# Sheet1.net
KiCad netlist of a schematic drawn in Altium Designer
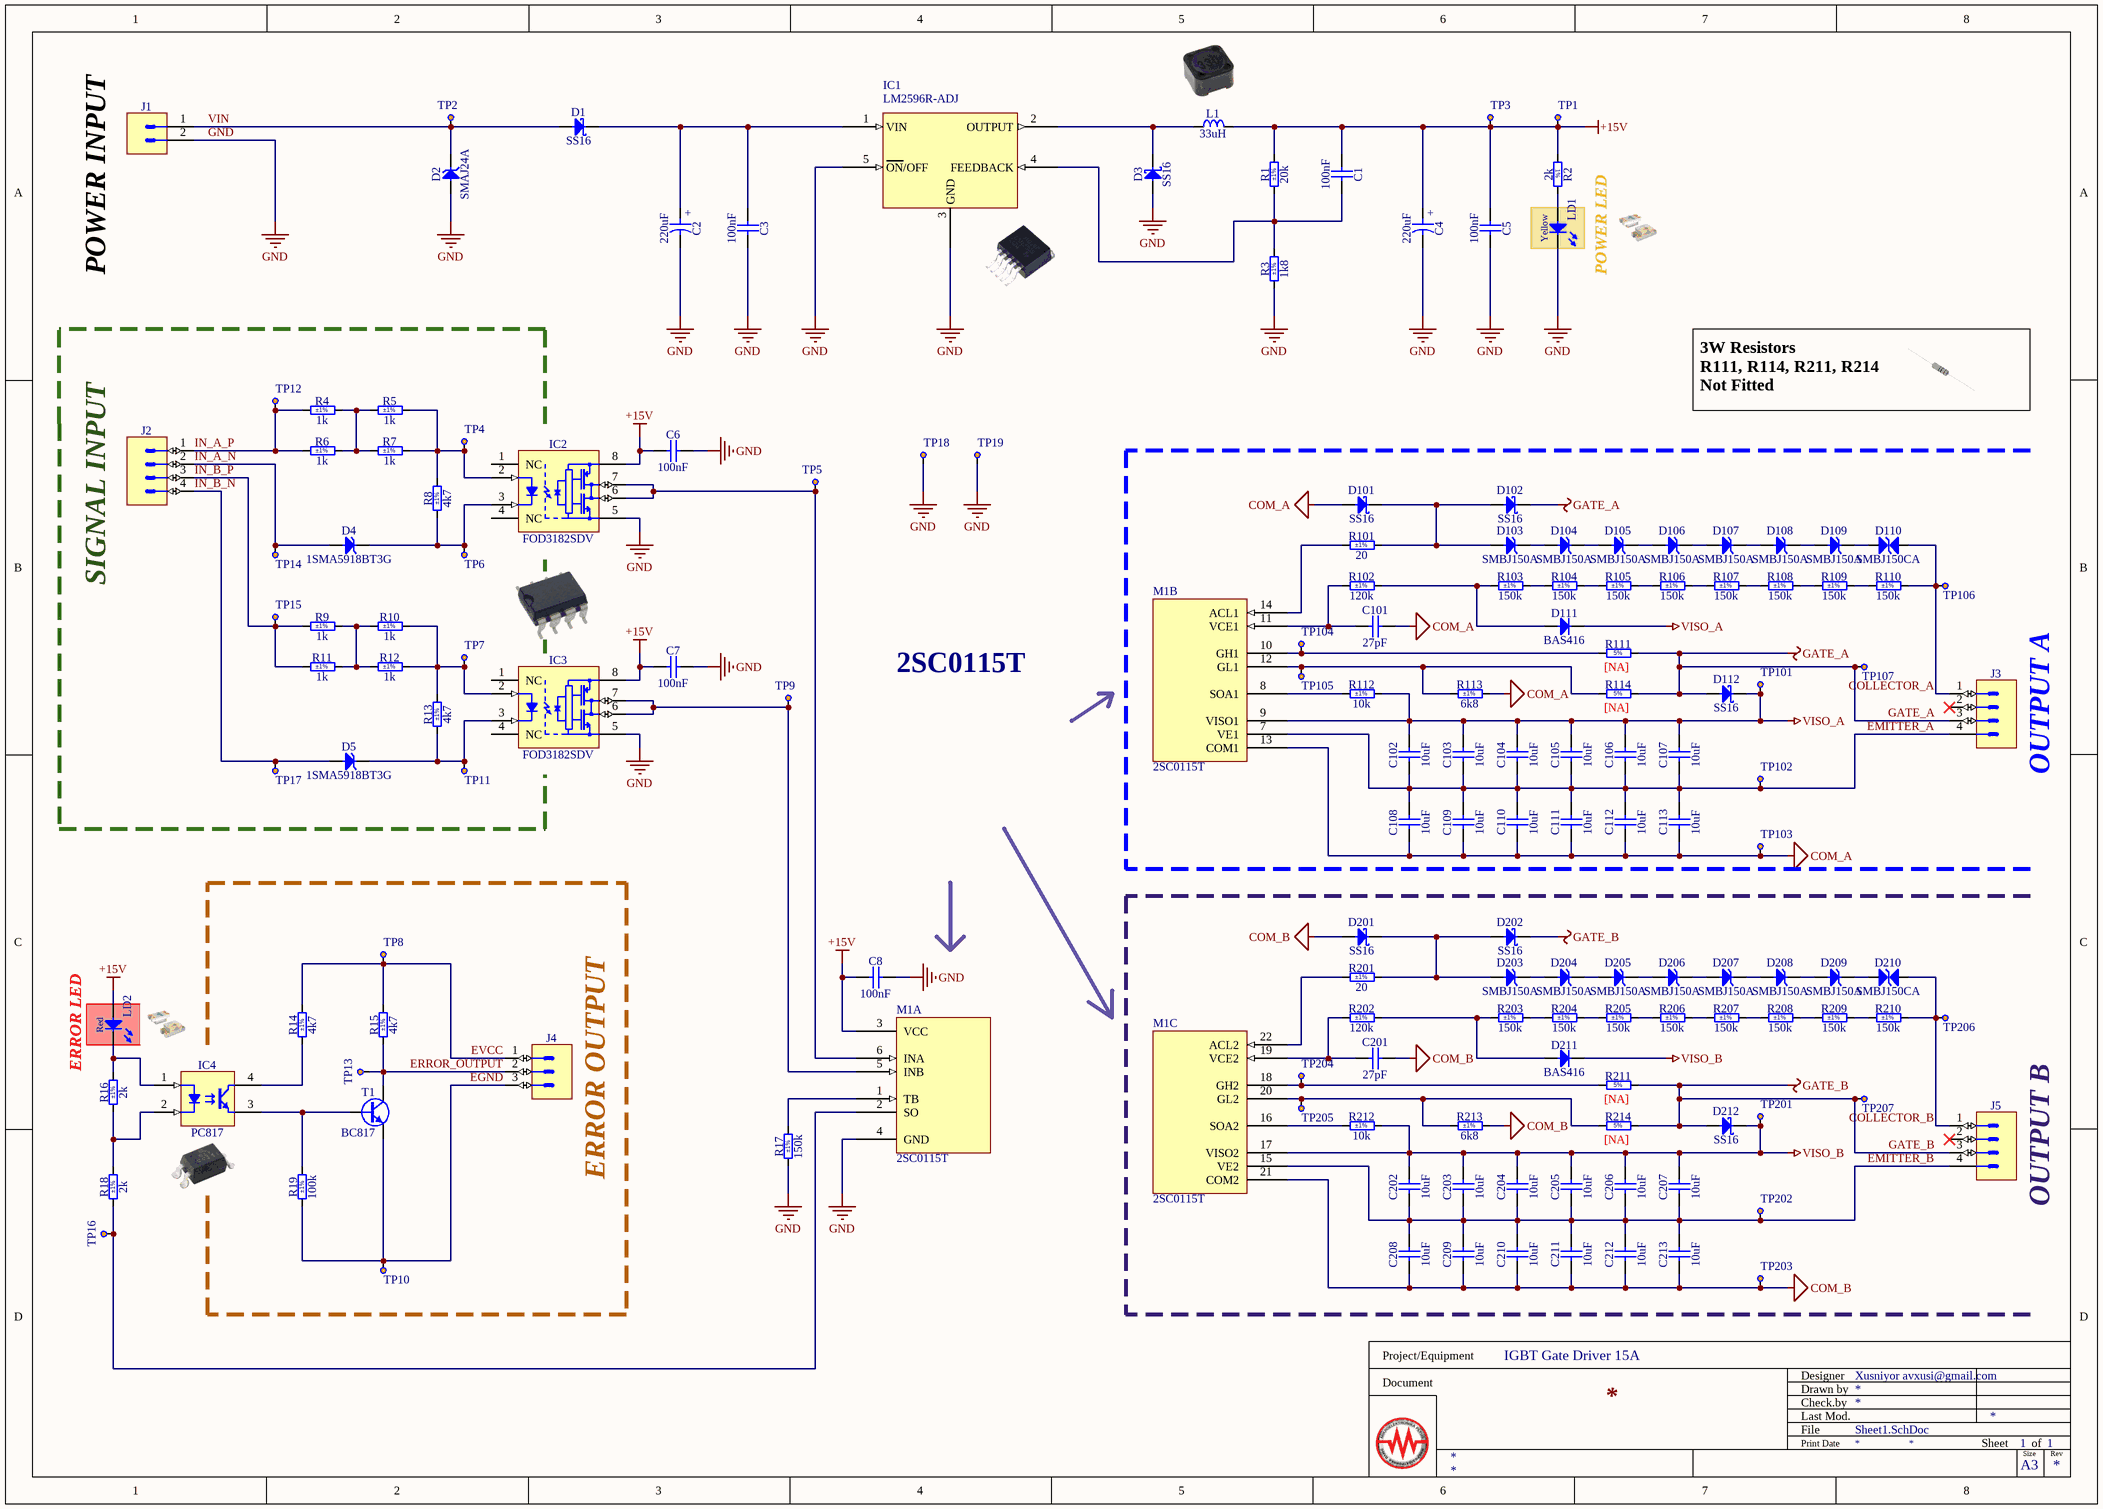
[diagram p0: Sheet1.SchDoc]

(export (version "E")
  (design (tool "Eeschema 10.0.6"))
  (components
    (comp (ref "C1")
      (value "100nF")
      (footprint "CAPC3216X140N")
      (description "Non-polarised capacitor")
      (fields
        (field (name "PART NUMBER") "CC1206_100NF_50V_10%_X7R")
        (field (name "VOLTAGE") "50V")
        (field (name "AUTHOR") "CERN DEM JLC")
      )
      (libsource (lib "Capacitors") (part "Capacitor - non polarized"))
    )
    (comp (ref "C2")
      (value "220uF")
      (footprint "CAPPR500-1050X1750")
      (description "Polarised capacitor")
      (fields
        (field (name "PART NUMBER") "CAER_220UF_35V_20%_500-1050X1750_LESR0R084")
        (field (name "VOLTAGE") "35V")
        (field (name "AUTHOR") "CERN DEM JLC")
      )
      (libsource (lib "Capacitors") (part "Capacitor - polarized"))
    )
    (comp (ref "C3")
      (value "100nF")
      (footprint "CAPC3216X140N")
      (description "Non-polarised capacitor")
      (fields
        (field (name "PART NUMBER") "CC1206_100NF_50V_10%_X7R")
        (field (name "VOLTAGE") "50V")
        (field (name "AUTHOR") "CERN DEM JLC")
      )
      (libsource (lib "Capacitors") (part "Capacitor - non polarized"))
    )
    (comp (ref "C4")
      (value "220uF")
      (footprint "CAPPR500-1050X1750")
      (description "Polarised capacitor")
      (fields
        (field (name "PART NUMBER") "CAER_220UF_35V_20%_500-1050X1750_LESR0R084")
        (field (name "VOLTAGE") "35V")
        (field (name "AUTHOR") "CERN DEM JLC")
      )
      (libsource (lib "Capacitors") (part "Capacitor - polarized"))
    )
    (comp (ref "C5")
      (value "100nF")
      (footprint "CAPC3216X140N")
      (description "Non-polarised capacitor")
      (fields
        (field (name "PART NUMBER") "CC1206_100NF_50V_10%_X7R")
        (field (name "VOLTAGE") "50V")
        (field (name "AUTHOR") "CERN DEM JLC")
      )
      (libsource (lib "Capacitors") (part "Capacitor - non polarized"))
    )
    (comp (ref "C6")
      (value "100nF")
      (footprint "CAPC3216X140N")
      (description "Non-polarised capacitor")
      (fields
        (field (name "PART NUMBER") "CC1206_100NF_50V_10%_X7R")
        (field (name "VOLTAGE") "50V")
        (field (name "AUTHOR") "CERN DEM JLC")
      )
      (libsource (lib "Capacitors") (part "Capacitor - non polarized"))
    )
    (comp (ref "C7")
      (value "100nF")
      (footprint "CAPC3216X140N")
      (description "Non-polarised capacitor")
      (fields
        (field (name "PART NUMBER") "CC1206_100NF_50V_10%_X7R")
        (field (name "VOLTAGE") "50V")
        (field (name "AUTHOR") "CERN DEM JLC")
      )
      (libsource (lib "Capacitors") (part "Capacitor - non polarized"))
    )
    (comp (ref "C8")
      (value "100nF")
      (footprint "CAPC3216X140N")
      (description "Non-polarised capacitor")
      (fields
        (field (name "PART NUMBER") "CC1206_100NF_50V_10%_X7R")
        (field (name "VOLTAGE") "50V")
        (field (name "AUTHOR") "CERN DEM JLC")
      )
      (libsource (lib "Capacitors") (part "Capacitor - non polarized"))
    )
    (comp (ref "C101")
      (value "27pF")
      (footprint "CAPC3216X140N")
      (description "Non-polarised capacitor")
      (fields
        (field (name "PART NUMBER") "CC1206_27PF_50V_5%_NP0")
        (field (name "VOLTAGE") "50V")
        (field (name "AUTHOR") "CERN DEM JLC")
      )
      (libsource (lib "Capacitors") (part "Capacitor - non polarized"))
    )
    (comp (ref "C102")
      (value "10uF")
      (footprint "CAPC3216X180N")
      (description "Non-polarised capacitor")
      (fields
        (field (name "PART NUMBER") "CC1206_10UF_25V_10%_X7R")
        (field (name "VOLTAGE") "25V")
        (field (name "AUTHOR") "CERN DEM JLC")
      )
      (libsource (lib "Capacitors") (part "Capacitor - non polarized"))
    )
    (comp (ref "C103")
      (value "10uF")
      (footprint "CAPC3216X180N")
      (description "Non-polarised capacitor")
      (fields
        (field (name "PART NUMBER") "CC1206_10UF_25V_10%_X7R")
        (field (name "VOLTAGE") "25V")
        (field (name "AUTHOR") "CERN DEM JLC")
      )
      (libsource (lib "Capacitors") (part "Capacitor - non polarized"))
    )
    (comp (ref "C104")
      (value "10uF")
      (footprint "CAPC3216X180N")
      (description "Non-polarised capacitor")
      (fields
        (field (name "PART NUMBER") "CC1206_10UF_25V_10%_X7R")
        (field (name "VOLTAGE") "25V")
        (field (name "AUTHOR") "CERN DEM JLC")
      )
      (libsource (lib "Capacitors") (part "Capacitor - non polarized"))
    )
    (comp (ref "C105")
      (value "10uF")
      (footprint "CAPC3216X180N")
      (description "Non-polarised capacitor")
      (fields
        (field (name "PART NUMBER") "CC1206_10UF_25V_10%_X7R")
        (field (name "VOLTAGE") "25V")
        (field (name "AUTHOR") "CERN DEM JLC")
      )
      (libsource (lib "Capacitors") (part "Capacitor - non polarized"))
    )
    (comp (ref "C106")
      (value "10uF")
      (footprint "CAPC3216X180N")
      (description "Non-polarised capacitor")
      (fields
        (field (name "PART NUMBER") "CC1206_10UF_25V_10%_X7R")
        (field (name "VOLTAGE") "25V")
        (field (name "AUTHOR") "CERN DEM JLC")
      )
      (libsource (lib "Capacitors") (part "Capacitor - non polarized"))
    )
    (comp (ref "C107")
      (value "10uF")
      (footprint "CAPC3216X180N")
      (description "Non-polarised capacitor")
      (fields
        (field (name "PART NUMBER") "CC1206_10UF_25V_10%_X7R")
        (field (name "VOLTAGE") "25V")
        (field (name "AUTHOR") "CERN DEM JLC")
      )
      (libsource (lib "Capacitors") (part "Capacitor - non polarized"))
    )
    (comp (ref "C108")
      (value "10uF")
      (footprint "CAPC3216X180N")
      (description "Non-polarised capacitor")
      (fields
        (field (name "PART NUMBER") "CC1206_10UF_25V_10%_X7R")
        (field (name "VOLTAGE") "25V")
        (field (name "AUTHOR") "CERN DEM JLC")
      )
      (libsource (lib "Capacitors") (part "Capacitor - non polarized"))
    )
    (comp (ref "C109")
      (value "10uF")
      (footprint "CAPC3216X180N")
      (description "Non-polarised capacitor")
      (fields
        (field (name "PART NUMBER") "CC1206_10UF_25V_10%_X7R")
        (field (name "VOLTAGE") "25V")
        (field (name "AUTHOR") "CERN DEM JLC")
      )
      (libsource (lib "Capacitors") (part "Capacitor - non polarized"))
    )
    (comp (ref "C110")
      (value "10uF")
      (footprint "CAPC3216X180N")
      (description "Non-polarised capacitor")
      (fields
        (field (name "PART NUMBER") "CC1206_10UF_25V_10%_X7R")
        (field (name "VOLTAGE") "25V")
        (field (name "AUTHOR") "CERN DEM JLC")
      )
      (libsource (lib "Capacitors") (part "Capacitor - non polarized"))
    )
    (comp (ref "C111")
      (value "10uF")
      (footprint "CAPC3216X180N")
      (description "Non-polarised capacitor")
      (fields
        (field (name "PART NUMBER") "CC1206_10UF_25V_10%_X7R")
        (field (name "VOLTAGE") "25V")
        (field (name "AUTHOR") "CERN DEM JLC")
      )
      (libsource (lib "Capacitors") (part "Capacitor - non polarized"))
    )
    (comp (ref "C112")
      (value "10uF")
      (footprint "CAPC3216X180N")
      (description "Non-polarised capacitor")
      (fields
        (field (name "PART NUMBER") "CC1206_10UF_25V_10%_X7R")
        (field (name "VOLTAGE") "25V")
        (field (name "AUTHOR") "CERN DEM JLC")
      )
      (libsource (lib "Capacitors") (part "Capacitor - non polarized"))
    )
    (comp (ref "C113")
      (value "10uF")
      (footprint "CAPC3216X180N")
      (description "Non-polarised capacitor")
      (fields
        (field (name "PART NUMBER") "CC1206_10UF_25V_10%_X7R")
        (field (name "VOLTAGE") "25V")
        (field (name "AUTHOR") "CERN DEM JLC")
      )
      (libsource (lib "Capacitors") (part "Capacitor - non polarized"))
    )
    (comp (ref "C201")
      (value "27pF")
      (footprint "CAPC3216X140N")
      (description "Non-polarised capacitor")
      (fields
        (field (name "PART NUMBER") "CC1206_27PF_50V_5%_NP0")
        (field (name "VOLTAGE") "50V")
        (field (name "AUTHOR") "CERN DEM JLC")
      )
      (libsource (lib "Capacitors") (part "Capacitor - non polarized"))
    )
    (comp (ref "C202")
      (value "10uF")
      (footprint "CAPC3216X180N")
      (description "Non-polarised capacitor")
      (fields
        (field (name "PART NUMBER") "CC1206_10UF_25V_10%_X7R")
        (field (name "VOLTAGE") "25V")
        (field (name "AUTHOR") "CERN DEM JLC")
      )
      (libsource (lib "Capacitors") (part "Capacitor - non polarized"))
    )
    (comp (ref "C203")
      (value "10uF")
      (footprint "CAPC3216X180N")
      (description "Non-polarised capacitor")
      (fields
        (field (name "PART NUMBER") "CC1206_10UF_25V_10%_X7R")
        (field (name "VOLTAGE") "25V")
        (field (name "AUTHOR") "CERN DEM JLC")
      )
      (libsource (lib "Capacitors") (part "Capacitor - non polarized"))
    )
    (comp (ref "C204")
      (value "10uF")
      (footprint "CAPC3216X180N")
      (description "Non-polarised capacitor")
      (fields
        (field (name "PART NUMBER") "CC1206_10UF_25V_10%_X7R")
        (field (name "VOLTAGE") "25V")
        (field (name "AUTHOR") "CERN DEM JLC")
      )
      (libsource (lib "Capacitors") (part "Capacitor - non polarized"))
    )
    (comp (ref "C205")
      (value "10uF")
      (footprint "CAPC3216X180N")
      (description "Non-polarised capacitor")
      (fields
        (field (name "PART NUMBER") "CC1206_10UF_25V_10%_X7R")
        (field (name "VOLTAGE") "25V")
        (field (name "AUTHOR") "CERN DEM JLC")
      )
      (libsource (lib "Capacitors") (part "Capacitor - non polarized"))
    )
    (comp (ref "C206")
      (value "10uF")
      (footprint "CAPC3216X180N")
      (description "Non-polarised capacitor")
      (fields
        (field (name "PART NUMBER") "CC1206_10UF_25V_10%_X7R")
        (field (name "VOLTAGE") "25V")
        (field (name "AUTHOR") "CERN DEM JLC")
      )
      (libsource (lib "Capacitors") (part "Capacitor - non polarized"))
    )
    (comp (ref "C207")
      (value "10uF")
      (footprint "CAPC3216X180N")
      (description "Non-polarised capacitor")
      (fields
        (field (name "PART NUMBER") "CC1206_10UF_25V_10%_X7R")
        (field (name "VOLTAGE") "25V")
        (field (name "AUTHOR") "CERN DEM JLC")
      )
      (libsource (lib "Capacitors") (part "Capacitor - non polarized"))
    )
    (comp (ref "C208")
      (value "10uF")
      (footprint "CAPC3216X180N")
      (description "Non-polarised capacitor")
      (fields
        (field (name "PART NUMBER") "CC1206_10UF_25V_10%_X7R")
        (field (name "VOLTAGE") "25V")
        (field (name "AUTHOR") "CERN DEM JLC")
      )
      (libsource (lib "Capacitors") (part "Capacitor - non polarized"))
    )
    (comp (ref "C209")
      (value "10uF")
      (footprint "CAPC3216X180N")
      (description "Non-polarised capacitor")
      (fields
        (field (name "PART NUMBER") "CC1206_10UF_25V_10%_X7R")
        (field (name "VOLTAGE") "25V")
        (field (name "AUTHOR") "CERN DEM JLC")
      )
      (libsource (lib "Capacitors") (part "Capacitor - non polarized"))
    )
    (comp (ref "C210")
      (value "10uF")
      (footprint "CAPC3216X180N")
      (description "Non-polarised capacitor")
      (fields
        (field (name "PART NUMBER") "CC1206_10UF_25V_10%_X7R")
        (field (name "VOLTAGE") "25V")
        (field (name "AUTHOR") "CERN DEM JLC")
      )
      (libsource (lib "Capacitors") (part "Capacitor - non polarized"))
    )
    (comp (ref "C211")
      (value "10uF")
      (footprint "CAPC3216X180N")
      (description "Non-polarised capacitor")
      (fields
        (field (name "PART NUMBER") "CC1206_10UF_25V_10%_X7R")
        (field (name "VOLTAGE") "25V")
        (field (name "AUTHOR") "CERN DEM JLC")
      )
      (libsource (lib "Capacitors") (part "Capacitor - non polarized"))
    )
    (comp (ref "C212")
      (value "10uF")
      (footprint "CAPC3216X180N")
      (description "Non-polarised capacitor")
      (fields
        (field (name "PART NUMBER") "CC1206_10UF_25V_10%_X7R")
        (field (name "VOLTAGE") "25V")
        (field (name "AUTHOR") "CERN DEM JLC")
      )
      (libsource (lib "Capacitors") (part "Capacitor - non polarized"))
    )
    (comp (ref "C213")
      (value "10uF")
      (footprint "CAPC3216X180N")
      (description "Non-polarised capacitor")
      (fields
        (field (name "PART NUMBER") "CC1206_10UF_25V_10%_X7R")
        (field (name "VOLTAGE") "25V")
        (field (name "AUTHOR") "CERN DEM JLC")
      )
      (libsource (lib "Capacitors") (part "Capacitor - non polarized"))
    )
    (comp (ref "D1")
      (value "SS16")
      (footprint "DIOM5127X229N")
      (description "Schottky Diode")
      (fields
        (field (name "VOLTAGE") "60V")
        (field (name "POWER") "1A")
        (field (name "AUTHOR") "CERN DEM JLC")
      )
      (libsource (lib "ICs And Semiconductors") (part "Diode Schottky"))
    )
    (comp (ref "D2")
      (value "SMAJ24A")
      (footprint "DIOM5226X262N")
      (description "Transient Voltage Suppressor Diode (Uni-Directional)")
      (fields
        (field (name "VOLTAGE") "24V")
        (field (name "POWER") "400W")
        (field (name "AUTHOR") "CERN DEM JLC")
      )
      (libsource (lib "ICs And Semiconductors") (part "Diode TVS Uni-Directional"))
    )
    (comp (ref "D3")
      (value "SS16")
      (footprint "DIOM5127X229N")
      (description "Schottky Diode")
      (fields
        (field (name "VOLTAGE") "60V")
        (field (name "POWER") "1A")
        (field (name "AUTHOR") "CERN DEM JLC")
      )
      (libsource (lib "ICs And Semiconductors") (part "Diode Schottky"))
    )
    (comp (ref "D4")
      (value "1SMA5918BT3G")
      (footprint "DIOM5226X220N")
      (description "Zener Diode")
      (fields
        (field (name "VOLTAGE") "5.1V")
        (field (name "POWER") "1.5W")
        (field (name "AUTHOR") "CERN DEM JLC")
      )
      (libsource (lib "ICs And Semiconductors") (part "Diode Zener"))
    )
    (comp (ref "D5")
      (value "1SMA5918BT3G")
      (footprint "DIOM5226X220N")
      (description "Zener Diode")
      (fields
        (field (name "VOLTAGE") "5.1V")
        (field (name "POWER") "1.5W")
        (field (name "AUTHOR") "CERN DEM JLC")
      )
      (libsource (lib "ICs And Semiconductors") (part "Diode Zener"))
    )
    (comp (ref "D101")
      (value "SS16")
      (footprint "DIOM5127X229N")
      (description "Schottky Diode")
      (fields
        (field (name "VOLTAGE") "60V")
        (field (name "POWER") "1A")
        (field (name "AUTHOR") "CERN DEM JLC")
      )
      (libsource (lib "ICs And Semiconductors") (part "Diode Schottky"))
    )
    (comp (ref "D102")
      (value "SS16")
      (footprint "DIOM5127X229N")
      (description "Schottky Diode")
      (fields
        (field (name "VOLTAGE") "60V")
        (field (name "POWER") "1A")
        (field (name "AUTHOR") "CERN DEM JLC")
      )
      (libsource (lib "ICs And Semiconductors") (part "Diode Schottky"))
    )
    (comp (ref "D103")
      (value "SMBJ150A")
      (footprint "DIOM5336X265N")
      (description "Transient Voltage Suppressor Diode (Uni-Directional)")
      (fields
        (field (name "VOLTAGE") "150V")
        (field (name "POWER") "600W")
        (field (name "AUTHOR") "CERN DEM MR")
      )
      (libsource (lib "ICs And Semiconductors") (part "Diode TVS Uni-Directional"))
    )
    (comp (ref "D104")
      (value "SMBJ150A")
      (footprint "DIOM5336X265N")
      (description "Transient Voltage Suppressor Diode (Uni-Directional)")
      (fields
        (field (name "VOLTAGE") "150V")
        (field (name "POWER") "600W")
        (field (name "AUTHOR") "CERN DEM MR")
      )
      (libsource (lib "ICs And Semiconductors") (part "Diode TVS Uni-Directional"))
    )
    (comp (ref "D105")
      (value "SMBJ150A")
      (footprint "DIOM5336X265N")
      (description "Transient Voltage Suppressor Diode (Uni-Directional)")
      (fields
        (field (name "VOLTAGE") "150V")
        (field (name "POWER") "600W")
        (field (name "AUTHOR") "CERN DEM MR")
      )
      (libsource (lib "ICs And Semiconductors") (part "Diode TVS Uni-Directional"))
    )
    (comp (ref "D106")
      (value "SMBJ150A")
      (footprint "DIOM5336X265N")
      (description "Transient Voltage Suppressor Diode (Uni-Directional)")
      (fields
        (field (name "VOLTAGE") "150V")
        (field (name "POWER") "600W")
        (field (name "AUTHOR") "CERN DEM MR")
      )
      (libsource (lib "ICs And Semiconductors") (part "Diode TVS Uni-Directional"))
    )
    (comp (ref "D107")
      (value "SMBJ150A")
      (footprint "DIOM5336X265N")
      (description "Transient Voltage Suppressor Diode (Uni-Directional)")
      (fields
        (field (name "VOLTAGE") "150V")
        (field (name "POWER") "600W")
        (field (name "AUTHOR") "CERN DEM MR")
      )
      (libsource (lib "ICs And Semiconductors") (part "Diode TVS Uni-Directional"))
    )
    (comp (ref "D108")
      (value "SMBJ150A")
      (footprint "DIOM5336X265N")
      (description "Transient Voltage Suppressor Diode (Uni-Directional)")
      (fields
        (field (name "VOLTAGE") "150V")
        (field (name "POWER") "600W")
        (field (name "AUTHOR") "CERN DEM MR")
      )
      (libsource (lib "ICs And Semiconductors") (part "Diode TVS Uni-Directional"))
    )
    (comp (ref "D109")
      (value "SMBJ150A")
      (footprint "DIOM5336X265N")
      (description "Transient Voltage Suppressor Diode (Uni-Directional)")
      (fields
        (field (name "VOLTAGE") "150V")
        (field (name "POWER") "600W")
        (field (name "AUTHOR") "CERN DEM MR")
      )
      (libsource (lib "ICs And Semiconductors") (part "Diode TVS Uni-Directional"))
    )
    (comp (ref "D110")
      (value "SMBJ150CA")
      (footprint "DIOM5336X265N")
      (description "Transient Voltage Suppressor Diode (Bi-Directional)")
      (fields
        (field (name "VOLTAGE") "150V")
        (field (name "POWER") "600W")
        (field (name "AUTHOR") "CERN DEM BC")
      )
      (libsource (lib "ICs And Semiconductors") (part "Diode TVS Bi-Directional"))
    )
    (comp (ref "D111")
      (value "BAS416")
      (footprint "SOD2512X110N")
      (description "Diode")
      (fields
        (field (name "VOLTAGE") "75V")
        (field (name "POWER") "200mA")
        (field (name "AUTHOR") "CERN DEM JLC")
      )
      (libsource (lib "ICs And Semiconductors") (part "Diode"))
    )
    (comp (ref "D112")
      (value "SS16")
      (footprint "DIOM5127X229N")
      (description "Schottky Diode")
      (fields
        (field (name "VOLTAGE") "60V")
        (field (name "POWER") "1A")
        (field (name "AUTHOR") "CERN DEM JLC")
      )
      (libsource (lib "ICs And Semiconductors") (part "Diode Schottky"))
    )
    (comp (ref "D201")
      (value "SS16")
      (footprint "DIOM5127X229N")
      (description "Schottky Diode")
      (fields
        (field (name "VOLTAGE") "60V")
        (field (name "POWER") "1A")
        (field (name "AUTHOR") "CERN DEM JLC")
      )
      (libsource (lib "ICs And Semiconductors") (part "Diode Schottky"))
    )
    (comp (ref "D202")
      (value "SS16")
      (footprint "DIOM5127X229N")
      (description "Schottky Diode")
      (fields
        (field (name "VOLTAGE") "60V")
        (field (name "POWER") "1A")
        (field (name "AUTHOR") "CERN DEM JLC")
      )
      (libsource (lib "ICs And Semiconductors") (part "Diode Schottky"))
    )
    (comp (ref "D203")
      (value "SMBJ150A")
      (footprint "DIOM5336X265N")
      (description "Transient Voltage Suppressor Diode (Uni-Directional)")
      (fields
        (field (name "VOLTAGE") "150V")
        (field (name "POWER") "600W")
        (field (name "AUTHOR") "CERN DEM MR")
      )
      (libsource (lib "ICs And Semiconductors") (part "Diode TVS Uni-Directional"))
    )
    (comp (ref "D204")
      (value "SMBJ150A")
      (footprint "DIOM5336X265N")
      (description "Transient Voltage Suppressor Diode (Uni-Directional)")
      (fields
        (field (name "VOLTAGE") "150V")
        (field (name "POWER") "600W")
        (field (name "AUTHOR") "CERN DEM MR")
      )
      (libsource (lib "ICs And Semiconductors") (part "Diode TVS Uni-Directional"))
    )
    (comp (ref "D205")
      (value "SMBJ150A")
      (footprint "DIOM5336X265N")
      (description "Transient Voltage Suppressor Diode (Uni-Directional)")
      (fields
        (field (name "VOLTAGE") "150V")
        (field (name "POWER") "600W")
        (field (name "AUTHOR") "CERN DEM MR")
      )
      (libsource (lib "ICs And Semiconductors") (part "Diode TVS Uni-Directional"))
    )
    (comp (ref "D206")
      (value "SMBJ150A")
      (footprint "DIOM5336X265N")
      (description "Transient Voltage Suppressor Diode (Uni-Directional)")
      (fields
        (field (name "VOLTAGE") "150V")
        (field (name "POWER") "600W")
        (field (name "AUTHOR") "CERN DEM MR")
      )
      (libsource (lib "ICs And Semiconductors") (part "Diode TVS Uni-Directional"))
    )
    (comp (ref "D207")
      (value "SMBJ150A")
      (footprint "DIOM5336X265N")
      (description "Transient Voltage Suppressor Diode (Uni-Directional)")
      (fields
        (field (name "VOLTAGE") "150V")
        (field (name "POWER") "600W")
        (field (name "AUTHOR") "CERN DEM MR")
      )
      (libsource (lib "ICs And Semiconductors") (part "Diode TVS Uni-Directional"))
    )
    (comp (ref "D208")
      (value "SMBJ150A")
      (footprint "DIOM5336X265N")
      (description "Transient Voltage Suppressor Diode (Uni-Directional)")
      (fields
        (field (name "VOLTAGE") "150V")
        (field (name "POWER") "600W")
        (field (name "AUTHOR") "CERN DEM MR")
      )
      (libsource (lib "ICs And Semiconductors") (part "Diode TVS Uni-Directional"))
    )
    (comp (ref "D209")
      (value "SMBJ150A")
      (footprint "DIOM5336X265N")
      (description "Transient Voltage Suppressor Diode (Uni-Directional)")
      (fields
        (field (name "VOLTAGE") "150V")
        (field (name "POWER") "600W")
        (field (name "AUTHOR") "CERN DEM MR")
      )
      (libsource (lib "ICs And Semiconductors") (part "Diode TVS Uni-Directional"))
    )
    (comp (ref "D210")
      (value "SMBJ150CA")
      (footprint "DIOM5336X265N")
      (description "Transient Voltage Suppressor Diode (Bi-Directional)")
      (fields
        (field (name "VOLTAGE") "150V")
        (field (name "POWER") "600W")
        (field (name "AUTHOR") "CERN DEM BC")
      )
      (libsource (lib "ICs And Semiconductors") (part "Diode TVS Bi-Directional"))
    )
    (comp (ref "D211")
      (value "BAS416")
      (footprint "SOD2512X110N")
      (description "Diode")
      (fields
        (field (name "VOLTAGE") "75V")
        (field (name "POWER") "200mA")
        (field (name "AUTHOR") "CERN DEM JLC")
      )
      (libsource (lib "ICs And Semiconductors") (part "Diode"))
    )
    (comp (ref "D212")
      (value "SS16")
      (footprint "DIOM5127X229N")
      (description "Schottky Diode")
      (fields
        (field (name "VOLTAGE") "60V")
        (field (name "POWER") "1A")
        (field (name "AUTHOR") "CERN DEM JLC")
      )
      (libsource (lib "ICs And Semiconductors") (part "Diode Schottky"))
    )
    (comp (ref "IC1")
      (value "LM2596R-ADJ")
      (footprint "TO-263-5:TO-263-5")
      (description "40V 3A TO-263-5 DC-DC Converters RoHS")
      (fields (field (name "MANUFACTURER") "HTC Korea TAEJIN Tech"))
      (libsource (lib "DC-DC") (part "LM2596"))
    )
    (comp (ref "IC2")
      (value "FOD3182SDV")
      (footprint "FAIRCHILD_8LD MDIP (OPTION S)")
      (description "Optocoupler")
      (fields (field (name "MANUFACTURER") "FAIRCHILD SEMICONDUCTOR") (field (name "AUTHOR") "CERN DEM JLC"))
      (libsource (lib "ICs And Semiconductors") (part "Optocoupler Type17"))
    )
    (comp (ref "IC3")
      (value "FOD3182SDV")
      (footprint "FAIRCHILD_8LD MDIP (OPTION S)")
      (description "Optocoupler")
      (fields (field (name "MANUFACTURER") "FAIRCHILD SEMICONDUCTOR") (field (name "AUTHOR") "CERN DEM JLC"))
      (libsource (lib "ICs And Semiconductors") (part "Optocoupler Type17"))
    )
    (comp (ref "IC4")
      (value "PC817")
      (footprint "FAIRCHILD_FOD817DSD")
      (description "Single Optocoupler")
      (fields
        (field (name "PART NUMBER") "FOD817DSD")
        (field (name "MANUFACTURER") "FAIRCHILD SEMICONDUCTOR")
        (field (name "AUTHOR") "CERN DEM JLC")
      )
      (libsource (lib "ICs And Semiconductors") (part "Optocoupler Type7"))
    )
    (comp (ref "J1")
      (value "~")
      (footprint "PHOENIX_1777073")
      (description "Connector 2 Male")
      (fields
        (field (name "PART NUMBER") "PHOENIX_1777073")
        (field (name "MANUFACTURER") "PHOENIX CONTACT")
        (field (name "AUTHOR") "CERN DEM BC")
      )
      (libsource (lib "Connectors") (part "Connector 2 Male"))
    )
    (comp (ref "J2")
      (value "~")
      (footprint "PHOENIX_1777099")
      (description "Connector 4 Male")
      (fields
        (field (name "PART NUMBER") "PHOENIX_1777099")
        (field (name "MANUFACTURER") "PHOENIX CONTACT")
        (field (name "AUTHOR") "CERN DEM JMW")
      )
      (libsource (lib "") (part "Connector 4 Male_1"))
    )
    (comp (ref "J3")
      (value "~")
      (footprint "PHOENIX_1777099")
      (description "Connector 4 Male")
      (fields
        (field (name "PART NUMBER") "PHOENIX_1777099")
        (field (name "MANUFACTURER") "PHOENIX CONTACT")
        (field (name "AUTHOR") "CERN DEM JMW")
      )
      (libsource (lib "Connectors") (part "Connector 4 Male"))
    )
    (comp (ref "J4")
      (value "~")
      (footprint "PHOENIX_1777086")
      (description "Connector 3 Male")
      (fields
        (field (name "PART NUMBER") "PHOENIX_1777086")
        (field (name "MANUFACTURER") "PHOENIX CONTACT")
        (field (name "AUTHOR") "CERN DEM JMW")
      )
      (libsource (lib "Connectors") (part "Connector 3 Male"))
    )
    (comp (ref "J5")
      (value "~")
      (footprint "PHOENIX_1777099")
      (description "Connector 4 Male")
      (fields
        (field (name "PART NUMBER") "PHOENIX_1777099")
        (field (name "MANUFACTURER") "PHOENIX CONTACT")
        (field (name "AUTHOR") "CERN DEM JMW")
      )
      (libsource (lib "Connectors") (part "Connector 4 Male"))
    )
    (comp (ref "L1")
      (value "33uH")
      (footprint "IND_BOURNS_PM127SH")
      (description "Inductor")
      (fields
        (field (name "PART NUMBER") "IND_33UH_20%_BOURNS_PM127SH")
        (field (name "POWER") "3.5A")
        (field (name "AUTHOR") "CERN DEM JLC")
      )
      (libsource (lib "Inductors & Transformers") (part "Inductor"))
    )
    (comp (ref "LD1")
      (value "Yellow")
      (footprint "LED_3MM_YELLOW_1C-2A")
      (description "LED Yellow 1C 2A")
      (fields
        (field (name "PART NUMBER") "LED_AVAGO_HLMP-1719")
        (field (name "MANUFACTURER") "AVAGO TECHNOLOGIES")
        (field (name "AUTHOR") "CERN DEM JLC")
      )
      (libsource (lib "ICs And Semiconductors") (part "LED Yellow 1C 2A"))
    )
    (comp (ref "LD2")
      (value "Red")
      (footprint "LED_3MM_RED_1C-2A")
      (description "LED Red 1C 2A")
      (fields
        (field (name "PART NUMBER") "LED_AVAGO_HLMP-1700")
        (field (name "MANUFACTURER") "AVAGO TECHNOLOGIES")
        (field (name "AUTHOR") "CERN DEM JLC")
      )
      (libsource (lib "ICs And Semiconductors") (part "LED Red 1C 2A"))
    )
    (comp (ref "M1")
      (value "2SC0115T")
      (footprint "2sc0115t:2sc0115t")
      (libsource (lib "2sc0115t") (part "2SC0115T"))
    )
    (comp (ref "R1")
      (value "20k")
      (footprint "RESC3216X65N")
      (description "Resistor - 1%")
      (fields
        (field (name "TOLERANCE") "±1%")
        (field (name "PART NUMBER") "R1206_20K_1%_0.25W_100PPM")
        (field (name "POWER") "0.25W")
        (field (name "AUTHOR") "CERN DEM JLC")
      )
      (libsource (lib "Resistors") (part "Resistor - 1%"))
    )
    (comp (ref "R2")
      (value "2k")
      (footprint "RESC3216X65N")
      (description "Resistor - 1%")
      (fields
        (field (name "PART NUMBER") "R1206_2K_1%_0.25W_100PPM")
        (field (name "POWER") "0.25W")
        (field (name "AUTHOR") "CERN DEM JLC")
      )
      (libsource (lib "Resistors") (part "Resistor - 1%"))
    )
    (comp (ref "R3")
      (value "1k8")
      (footprint "RESC3216X65N")
      (description "Resistor - 1%")
      (fields
        (field (name "TOLERANCE") "±1%")
        (field (name "PART NUMBER") "R1206_1K8_1%_0.25W_100PPM")
        (field (name "POWER") "0.25W")
        (field (name "AUTHOR") "CERN DEM JLC")
      )
      (libsource (lib "Resistors") (part "Resistor - 1%"))
    )
    (comp (ref "R4")
      (value "1k")
      (footprint "RESC3216X65N")
      (description "Resistor - 1%")
      (fields
        (field (name "TOLERANCE") "±1%")
        (field (name "PART NUMBER") "R1206_1K_1%_0.25W_100PPM")
        (field (name "POWER") "0.25W")
        (field (name "AUTHOR") "CERN DEM JLC")
      )
      (libsource (lib "Resistors") (part "Resistor - 1%"))
    )
    (comp (ref "R5")
      (value "1k")
      (footprint "RESC3216X65N")
      (description "Resistor - 1%")
      (fields
        (field (name "TOLERANCE") "±1%")
        (field (name "PART NUMBER") "R1206_1K_1%_0.25W_100PPM")
        (field (name "POWER") "0.25W")
        (field (name "AUTHOR") "CERN DEM JLC")
      )
      (libsource (lib "Resistors") (part "Resistor - 1%"))
    )
    (comp (ref "R6")
      (value "1k")
      (footprint "RESC3216X65N")
      (description "Resistor - 1%")
      (fields
        (field (name "TOLERANCE") "±1%")
        (field (name "PART NUMBER") "R1206_1K_1%_0.25W_100PPM")
        (field (name "POWER") "0.25W")
        (field (name "AUTHOR") "CERN DEM JLC")
      )
      (libsource (lib "Resistors") (part "Resistor - 1%"))
    )
    (comp (ref "R7")
      (value "1k")
      (footprint "RESC3216X65N")
      (description "Resistor - 1%")
      (fields
        (field (name "TOLERANCE") "±1%")
        (field (name "PART NUMBER") "R1206_1K_1%_0.25W_100PPM")
        (field (name "POWER") "0.25W")
        (field (name "AUTHOR") "CERN DEM JLC")
      )
      (libsource (lib "Resistors") (part "Resistor - 1%"))
    )
    (comp (ref "R8")
      (value "4k7")
      (footprint "RESC3216X65N")
      (description "Resistor - 1%")
      (fields
        (field (name "TOLERANCE") "±1%")
        (field (name "PART NUMBER") "R1206_4K7_1%_0.25W_100PPM")
        (field (name "POWER") "0.25W")
        (field (name "AUTHOR") "CERN DEM JLC")
      )
      (libsource (lib "Resistors") (part "Resistor - 1%"))
    )
    (comp (ref "R9")
      (value "1k")
      (footprint "RESC3216X65N")
      (description "Resistor - 1%")
      (fields
        (field (name "TOLERANCE") "±1%")
        (field (name "PART NUMBER") "R1206_1K_1%_0.25W_100PPM")
        (field (name "POWER") "0.25W")
        (field (name "AUTHOR") "CERN DEM JLC")
      )
      (libsource (lib "Resistors") (part "Resistor - 1%"))
    )
    (comp (ref "R10")
      (value "1k")
      (footprint "RESC3216X65N")
      (description "Resistor - 1%")
      (fields
        (field (name "TOLERANCE") "±1%")
        (field (name "PART NUMBER") "R1206_1K_1%_0.25W_100PPM")
        (field (name "POWER") "0.25W")
        (field (name "AUTHOR") "CERN DEM JLC")
      )
      (libsource (lib "Resistors") (part "Resistor - 1%"))
    )
    (comp (ref "R11")
      (value "1k")
      (footprint "RESC3216X65N")
      (description "Resistor - 1%")
      (fields
        (field (name "TOLERANCE") "±1%")
        (field (name "PART NUMBER") "R1206_1K_1%_0.25W_100PPM")
        (field (name "POWER") "0.25W")
        (field (name "AUTHOR") "CERN DEM JLC")
      )
      (libsource (lib "Resistors") (part "Resistor - 1%"))
    )
    (comp (ref "R12")
      (value "1k")
      (footprint "RESC3216X65N")
      (description "Resistor - 1%")
      (fields
        (field (name "TOLERANCE") "±1%")
        (field (name "PART NUMBER") "R1206_1K_1%_0.25W_100PPM")
        (field (name "POWER") "0.25W")
        (field (name "AUTHOR") "CERN DEM JLC")
      )
      (libsource (lib "Resistors") (part "Resistor - 1%"))
    )
    (comp (ref "R13")
      (value "4k7")
      (footprint "RESC3216X65N")
      (description "Resistor - 1%")
      (fields
        (field (name "TOLERANCE") "±1%")
        (field (name "PART NUMBER") "R1206_4K7_1%_0.25W_100PPM")
        (field (name "POWER") "0.25W")
        (field (name "AUTHOR") "CERN DEM JLC")
      )
      (libsource (lib "Resistors") (part "Resistor - 1%"))
    )
    (comp (ref "R14")
      (value "4k7")
      (footprint "RESC3216X65N")
      (description "Resistor - 1%")
      (fields
        (field (name "TOLERANCE") "±1%")
        (field (name "PART NUMBER") "R1206_4K7_1%_0.25W_100PPM")
        (field (name "POWER") "0.25W")
        (field (name "AUTHOR") "CERN DEM JLC")
      )
      (libsource (lib "Resistors") (part "Resistor - 1%"))
    )
    (comp (ref "R15")
      (value "4k7")
      (footprint "RESC3216X65N")
      (description "Resistor - 1%")
      (fields
        (field (name "TOLERANCE") "±1%")
        (field (name "PART NUMBER") "R1206_4K7_1%_0.25W_100PPM")
        (field (name "POWER") "0.25W")
        (field (name "AUTHOR") "CERN DEM JLC")
      )
      (libsource (lib "Resistors") (part "Resistor - 1%"))
    )
    (comp (ref "R16")
      (value "2k")
      (footprint "RESC3216X70N")
      (description "Resistor - 1%")
      (fields
        (field (name "TOLERANCE") "±1%")
        (field (name "PART NUMBER") "R1206_2K_1%_0.33W_200PPM_KOA_SG73S2BTTD2001F")
        (field (name "POWER") "0.33W")
        (field (name "AUTHOR") "CERN DEM JMW")
      )
      (libsource (lib "Resistors") (part "Resistor - 1%"))
    )
    (comp (ref "R17")
      (value "150k")
      (footprint "RESC3216X65N")
      (description "Resistor - 1%")
      (fields
        (field (name "TOLERANCE") "±1%")
        (field (name "PART NUMBER") "R1206_150K_1%_0.25W_100PPM")
        (field (name "POWER") "0.25W")
        (field (name "AUTHOR") "CERN DEM JLC")
      )
      (libsource (lib "Resistors") (part "Resistor - 1%"))
    )
    (comp (ref "R18")
      (value "2k")
      (footprint "RESC3216X70N")
      (description "Resistor - 1%")
      (fields
        (field (name "TOLERANCE") "±1%")
        (field (name "PART NUMBER") "R1206_2K_1%_0.33W_200PPM_KOA_SG73S2BTTD2001F")
        (field (name "POWER") "0.33W")
        (field (name "AUTHOR") "CERN DEM JMW")
      )
      (libsource (lib "Resistors") (part "Resistor - 1%"))
    )
    (comp (ref "R19")
      (value "100k")
      (footprint "RESC3216X65N")
      (description "Resistor - 1%")
      (fields
        (field (name "TOLERANCE") "±1%")
        (field (name "PART NUMBER") "R1206_100K_1%_0.25W_100PPM")
        (field (name "POWER") "0.25W")
        (field (name "AUTHOR") "CERN DEM JLC")
      )
      (libsource (lib "Resistors") (part "Resistor - 1%"))
    )
    (comp (ref "R101")
      (value "20")
      (footprint "RESC3216X65N")
      (description "Resistor - 1%")
      (fields
        (field (name "TOLERANCE") "±1%")
        (field (name "PART NUMBER") "R1206_20R_1%_0.25W_100PPM")
        (field (name "POWER") "0.25W")
        (field (name "AUTHOR") "CERN DEM JLC")
      )
      (libsource (lib "Resistors") (part "Resistor - 1%"))
    )
    (comp (ref "R102")
      (value "120k")
      (footprint "RESC3216X65N")
      (description "Resistor - 1%")
      (fields
        (field (name "TOLERANCE") "±1%")
        (field (name "PART NUMBER") "R1206_120K_1%_0.25W_100PPM")
        (field (name "POWER") "0.25W")
        (field (name "AUTHOR") "CERN DEM JLC")
      )
      (libsource (lib "Resistors") (part "Resistor - 1%"))
    )
    (comp (ref "R103")
      (value "150k")
      (footprint "RESC3216X65N")
      (description "Resistor - 1%")
      (fields
        (field (name "TOLERANCE") "±1%")
        (field (name "PART NUMBER") "R1206_150K_1%_0.25W_100PPM")
        (field (name "POWER") "0.25W")
        (field (name "AUTHOR") "CERN DEM JLC")
      )
      (libsource (lib "Resistors") (part "Resistor - 1%"))
    )
    (comp (ref "R104")
      (value "150k")
      (footprint "RESC3216X65N")
      (description "Resistor - 1%")
      (fields
        (field (name "TOLERANCE") "±1%")
        (field (name "PART NUMBER") "R1206_150K_1%_0.25W_100PPM")
        (field (name "POWER") "0.25W")
        (field (name "AUTHOR") "CERN DEM JLC")
      )
      (libsource (lib "Resistors") (part "Resistor - 1%"))
    )
    (comp (ref "R105")
      (value "150k")
      (footprint "RESC3216X65N")
      (description "Resistor - 1%")
      (fields
        (field (name "TOLERANCE") "±1%")
        (field (name "PART NUMBER") "R1206_150K_1%_0.25W_100PPM")
        (field (name "POWER") "0.25W")
        (field (name "AUTHOR") "CERN DEM JLC")
      )
      (libsource (lib "Resistors") (part "Resistor - 1%"))
    )
    (comp (ref "R106")
      (value "150k")
      (footprint "RESC3216X65N")
      (description "Resistor - 1%")
      (fields
        (field (name "TOLERANCE") "±1%")
        (field (name "PART NUMBER") "R1206_150K_1%_0.25W_100PPM")
        (field (name "POWER") "0.25W")
        (field (name "AUTHOR") "CERN DEM JLC")
      )
      (libsource (lib "Resistors") (part "Resistor - 1%"))
    )
    (comp (ref "R107")
      (value "150k")
      (footprint "RESC3216X65N")
      (description "Resistor - 1%")
      (fields
        (field (name "TOLERANCE") "±1%")
        (field (name "PART NUMBER") "R1206_150K_1%_0.25W_100PPM")
        (field (name "POWER") "0.25W")
        (field (name "AUTHOR") "CERN DEM JLC")
      )
      (libsource (lib "Resistors") (part "Resistor - 1%"))
    )
    (comp (ref "R108")
      (value "150k")
      (footprint "RESC3216X65N")
      (description "Resistor - 1%")
      (fields
        (field (name "TOLERANCE") "±1%")
        (field (name "PART NUMBER") "R1206_150K_1%_0.25W_100PPM")
        (field (name "POWER") "0.25W")
        (field (name "AUTHOR") "CERN DEM JLC")
      )
      (libsource (lib "Resistors") (part "Resistor - 1%"))
    )
    (comp (ref "R109")
      (value "150k")
      (footprint "RESC3216X65N")
      (description "Resistor - 1%")
      (fields
        (field (name "TOLERANCE") "±1%")
        (field (name "PART NUMBER") "R1206_150K_1%_0.25W_100PPM")
        (field (name "POWER") "0.25W")
        (field (name "AUTHOR") "CERN DEM JLC")
      )
      (libsource (lib "Resistors") (part "Resistor - 1%"))
    )
    (comp (ref "R110")
      (value "150k")
      (footprint "RESC3216X65N")
      (description "Resistor - 1%")
      (fields
        (field (name "TOLERANCE") "±1%")
        (field (name "PART NUMBER") "R1206_150K_1%_0.25W_100PPM")
        (field (name "POWER") "0.25W")
        (field (name "AUTHOR") "CERN DEM JLC")
      )
      (libsource (lib "Resistors") (part "Resistor - 1%"))
    )
    (comp (ref "R111")
      (value "5R6")
      (footprint "RES2286-1670X520")
      (description "Resistor - 5%")
      (fields
        (field (name "PART NUMBER") "RMF_5R6_5%_3W_250PPM_2286-1670X520")
        (field (name "POWER") "3W")
        (field (name "AUTHOR") "CERN DEM JLC")
      )
      (libsource (lib "Resistors") (part "Resistor - 5%"))
    )
    (comp (ref "R112")
      (value "10k")
      (footprint "RESC3216X65N")
      (description "Resistor - 1%")
      (fields
        (field (name "TOLERANCE") "±1%")
        (field (name "PART NUMBER") "R1206_10K_1%_0.25W_100PPM")
        (field (name "POWER") "0.25W")
        (field (name "AUTHOR") "CERN DEM JLC")
      )
      (libsource (lib "Resistors") (part "Resistor - 1%"))
    )
    (comp (ref "R113")
      (value "6k8")
      (footprint "RESC3216X65N")
      (description "Resistor - 1%")
      (fields
        (field (name "TOLERANCE") "±1%")
        (field (name "PART NUMBER") "R1206_6K8_1%_0.25W_100PPM")
        (field (name "POWER") "0.25W")
        (field (name "AUTHOR") "CERN DEM JLC")
      )
      (libsource (lib "Resistors") (part "Resistor - 1%"))
    )
    (comp (ref "R114")
      (value "5R6")
      (footprint "RES2286-1670X520")
      (description "Resistor - 5%")
      (fields
        (field (name "PART NUMBER") "RMF_5R6_5%_3W_250PPM_2286-1670X520")
        (field (name "POWER") "3W")
        (field (name "AUTHOR") "CERN DEM JLC")
      )
      (libsource (lib "Resistors") (part "Resistor - 5%"))
    )
    (comp (ref "R201")
      (value "20")
      (footprint "RESC3216X65N")
      (description "Resistor - 1%")
      (fields
        (field (name "TOLERANCE") "±1%")
        (field (name "PART NUMBER") "R1206_20R_1%_0.25W_100PPM")
        (field (name "POWER") "0.25W")
        (field (name "AUTHOR") "CERN DEM JLC")
      )
      (libsource (lib "Resistors") (part "Resistor - 1%"))
    )
    (comp (ref "R202")
      (value "120k")
      (footprint "RESC3216X65N")
      (description "Resistor - 1%")
      (fields
        (field (name "TOLERANCE") "±1%")
        (field (name "PART NUMBER") "R1206_120K_1%_0.25W_100PPM")
        (field (name "POWER") "0.25W")
        (field (name "AUTHOR") "CERN DEM JLC")
      )
      (libsource (lib "Resistors") (part "Resistor - 1%"))
    )
    (comp (ref "R203")
      (value "150k")
      (footprint "RESC3216X65N")
      (description "Resistor - 1%")
      (fields
        (field (name "TOLERANCE") "±1%")
        (field (name "PART NUMBER") "R1206_150K_1%_0.25W_100PPM")
        (field (name "POWER") "0.25W")
        (field (name "AUTHOR") "CERN DEM JLC")
      )
      (libsource (lib "Resistors") (part "Resistor - 1%"))
    )
    (comp (ref "R204")
      (value "150k")
      (footprint "RESC3216X65N")
      (description "Resistor - 1%")
      (fields
        (field (name "TOLERANCE") "±1%")
        (field (name "PART NUMBER") "R1206_150K_1%_0.25W_100PPM")
        (field (name "POWER") "0.25W")
        (field (name "AUTHOR") "CERN DEM JLC")
      )
      (libsource (lib "Resistors") (part "Resistor - 1%"))
    )
    (comp (ref "R205")
      (value "150k")
      (footprint "RESC3216X65N")
      (description "Resistor - 1%")
      (fields
        (field (name "TOLERANCE") "±1%")
        (field (name "PART NUMBER") "R1206_150K_1%_0.25W_100PPM")
        (field (name "POWER") "0.25W")
        (field (name "AUTHOR") "CERN DEM JLC")
      )
      (libsource (lib "Resistors") (part "Resistor - 1%"))
    )
    (comp (ref "R206")
      (value "150k")
      (footprint "RESC3216X65N")
      (description "Resistor - 1%")
      (fields
        (field (name "TOLERANCE") "±1%")
        (field (name "PART NUMBER") "R1206_150K_1%_0.25W_100PPM")
        (field (name "POWER") "0.25W")
        (field (name "AUTHOR") "CERN DEM JLC")
      )
      (libsource (lib "Resistors") (part "Resistor - 1%"))
    )
    (comp (ref "R207")
      (value "150k")
      (footprint "RESC3216X65N")
      (description "Resistor - 1%")
      (fields
        (field (name "TOLERANCE") "±1%")
        (field (name "PART NUMBER") "R1206_150K_1%_0.25W_100PPM")
        (field (name "POWER") "0.25W")
        (field (name "AUTHOR") "CERN DEM JLC")
      )
      (libsource (lib "Resistors") (part "Resistor - 1%"))
    )
    (comp (ref "R208")
      (value "150k")
      (footprint "RESC3216X65N")
      (description "Resistor - 1%")
      (fields
        (field (name "TOLERANCE") "±1%")
        (field (name "PART NUMBER") "R1206_150K_1%_0.25W_100PPM")
        (field (name "POWER") "0.25W")
        (field (name "AUTHOR") "CERN DEM JLC")
      )
      (libsource (lib "Resistors") (part "Resistor - 1%"))
    )
    (comp (ref "R209")
      (value "150k")
      (footprint "RESC3216X65N")
      (description "Resistor - 1%")
      (fields
        (field (name "TOLERANCE") "±1%")
        (field (name "PART NUMBER") "R1206_150K_1%_0.25W_100PPM")
        (field (name "POWER") "0.25W")
        (field (name "AUTHOR") "CERN DEM JLC")
      )
      (libsource (lib "Resistors") (part "Resistor - 1%"))
    )
    (comp (ref "R210")
      (value "150k")
      (footprint "RESC3216X65N")
      (description "Resistor - 1%")
      (fields
        (field (name "TOLERANCE") "±1%")
        (field (name "PART NUMBER") "R1206_150K_1%_0.25W_100PPM")
        (field (name "POWER") "0.25W")
        (field (name "AUTHOR") "CERN DEM JLC")
      )
      (libsource (lib "Resistors") (part "Resistor - 1%"))
    )
    (comp (ref "R211")
      (value "5R6")
      (footprint "RES2286-1670X520")
      (description "Resistor - 5%")
      (fields
        (field (name "PART NUMBER") "RMF_5R6_5%_3W_250PPM_2286-1670X520")
        (field (name "POWER") "3W")
        (field (name "AUTHOR") "CERN DEM JLC")
      )
      (libsource (lib "Resistors") (part "Resistor - 5%"))
    )
    (comp (ref "R212")
      (value "10k")
      (footprint "RESC3216X65N")
      (description "Resistor - 1%")
      (fields
        (field (name "TOLERANCE") "±1%")
        (field (name "PART NUMBER") "R1206_10K_1%_0.25W_100PPM")
        (field (name "POWER") "0.25W")
        (field (name "AUTHOR") "CERN DEM JLC")
      )
      (libsource (lib "Resistors") (part "Resistor - 1%"))
    )
    (comp (ref "R213")
      (value "6k8")
      (footprint "RESC3216X65N")
      (description "Resistor - 1%")
      (fields
        (field (name "TOLERANCE") "±1%")
        (field (name "PART NUMBER") "R1206_6K8_1%_0.25W_100PPM")
        (field (name "POWER") "0.25W")
        (field (name "AUTHOR") "CERN DEM JLC")
      )
      (libsource (lib "Resistors") (part "Resistor - 1%"))
    )
    (comp (ref "R214")
      (value "5R6")
      (footprint "RES2286-1670X520")
      (description "Resistor - 5%")
      (fields
        (field (name "PART NUMBER") "RMF_5R6_5%_3W_250PPM_2286-1670X520")
        (field (name "POWER") "3W")
        (field (name "AUTHOR") "CERN DEM JLC")
      )
      (libsource (lib "Resistors") (part "Resistor - 5%"))
    )
    (comp (ref "T1")
      (value "BC817")
      (footprint "SOT95P230X110-3N")
      (description "NPN Transistor")
      (fields (field (name "MANUFACTURER") "NXP SEMICONDUCTORS") (field (name "AUTHOR") "CERN DEM JLC"))
      (libsource (lib "ICs And Semiconductors") (part "NPN B1 E2 C3"))
    )
    (comp (ref "TP1")
      (value "Test_point")
      (footprint "fromST:TP_C40")
      (description "Test point")
      (fields (field (name "PUBLISHER") "Altium Limited"))
      (libsource (lib "Sajad_Altium_Library") (part "Test point"))
    )
    (comp (ref "TP2")
      (value "Test_point")
      (footprint "fromST:TP_C40")
      (description "Test point")
      (fields (field (name "PUBLISHER") "Altium Limited"))
      (libsource (lib "Sajad_Altium_Library") (part "Test point"))
    )
    (comp (ref "TP3")
      (value "Test_point")
      (footprint "fromST:TP_C40")
      (description "Test point")
      (fields (field (name "PUBLISHER") "Altium Limited"))
      (libsource (lib "Sajad_Altium_Library") (part "Test point"))
    )
    (comp (ref "TP4")
      (value "Test_point")
      (footprint "fromST:TP_C40")
      (description "Test point")
      (fields (field (name "PUBLISHER") "Altium Limited"))
      (libsource (lib "Sajad_Altium_Library") (part "Test point"))
    )
    (comp (ref "TP5")
      (value "Test_point")
      (footprint "fromST:TP_C40")
      (description "Test point")
      (fields (field (name "PUBLISHER") "Altium Limited"))
      (libsource (lib "Sajad_Altium_Library") (part "Test point"))
    )
    (comp (ref "TP6")
      (value "Test_point")
      (footprint "fromST:TP_C40")
      (description "Test point")
      (fields (field (name "PUBLISHER") "Altium Limited"))
      (libsource (lib "Sajad_Altium_Library") (part "Test point"))
    )
    (comp (ref "TP7")
      (value "Test_point")
      (footprint "fromST:TP_C40")
      (description "Test point")
      (fields (field (name "PUBLISHER") "Altium Limited"))
      (libsource (lib "Sajad_Altium_Library") (part "Test point"))
    )
    (comp (ref "TP8")
      (value "Test_point")
      (footprint "fromST:TP_C40")
      (description "Test point")
      (fields (field (name "PUBLISHER") "Altium Limited"))
      (libsource (lib "Sajad_Altium_Library") (part "Test point"))
    )
    (comp (ref "TP9")
      (value "Test_point")
      (footprint "fromST:TP_C40")
      (description "Test point")
      (fields (field (name "PUBLISHER") "Altium Limited"))
      (libsource (lib "Sajad_Altium_Library") (part "Test point"))
    )
    (comp (ref "TP10")
      (value "Test_point")
      (footprint "fromST:TP_C40")
      (description "Test point")
      (fields (field (name "PUBLISHER") "Altium Limited"))
      (libsource (lib "Sajad_Altium_Library") (part "Test point"))
    )
    (comp (ref "TP11")
      (value "Test_point")
      (footprint "fromST:TP_C40")
      (description "Test point")
      (fields (field (name "PUBLISHER") "Altium Limited"))
      (libsource (lib "Sajad_Altium_Library") (part "Test point"))
    )
    (comp (ref "TP12")
      (value "Test_point")
      (footprint "fromST:TP_C40")
      (description "Test point")
      (fields (field (name "PUBLISHER") "Altium Limited"))
      (libsource (lib "Sajad_Altium_Library") (part "Test point"))
    )
    (comp (ref "TP13")
      (value "Test_point")
      (footprint "fromST:TP_C40")
      (description "Test point")
      (fields (field (name "PUBLISHER") "Altium Limited"))
      (libsource (lib "Sajad_Altium_Library") (part "Test point"))
    )
    (comp (ref "TP14")
      (value "Test_point")
      (footprint "fromST:TP_C40")
      (description "Test point")
      (fields (field (name "PUBLISHER") "Altium Limited"))
      (libsource (lib "Sajad_Altium_Library") (part "Test point"))
    )
    (comp (ref "TP15")
      (value "Test_point")
      (footprint "fromST:TP_C40")
      (description "Test point")
      (fields (field (name "PUBLISHER") "Altium Limited"))
      (libsource (lib "Sajad_Altium_Library") (part "Test point"))
    )
    (comp (ref "TP16")
      (value "Test_point")
      (footprint "fromST:TP_C40")
      (description "Test point")
      (fields (field (name "PUBLISHER") "Altium Limited"))
      (libsource (lib "Sajad_Altium_Library") (part "Test point"))
    )
    (comp (ref "TP17")
      (value "Test_point")
      (footprint "fromST:TP_C40")
      (description "Test point")
      (fields (field (name "PUBLISHER") "Altium Limited"))
      (libsource (lib "Sajad_Altium_Library") (part "Test point"))
    )
    (comp (ref "TP18")
      (value "Test_point")
      (footprint "fromST:TP_C40")
      (description "Test point")
      (fields (field (name "PUBLISHER") "Altium Limited"))
      (libsource (lib "Sajad_Altium_Library") (part "Test point"))
    )
    (comp (ref "TP19")
      (value "Test_point")
      (footprint "fromST:TP_C40")
      (description "Test point")
      (fields (field (name "PUBLISHER") "Altium Limited"))
      (libsource (lib "Sajad_Altium_Library") (part "Test point"))
    )
    (comp (ref "TP101")
      (value "Test_point")
      (footprint "fromST:TP_C40")
      (description "Test point")
      (fields (field (name "PUBLISHER") "Altium Limited"))
      (libsource (lib "Sajad_Altium_Library") (part "Test point"))
    )
    (comp (ref "TP102")
      (value "Test_point")
      (footprint "fromST:TP_C40")
      (description "Test point")
      (fields (field (name "PUBLISHER") "Altium Limited"))
      (libsource (lib "Sajad_Altium_Library") (part "Test point"))
    )
    (comp (ref "TP103")
      (value "Test_point")
      (footprint "fromST:TP_C40")
      (description "Test point")
      (fields (field (name "PUBLISHER") "Altium Limited"))
      (libsource (lib "Sajad_Altium_Library") (part "Test point"))
    )
    (comp (ref "TP104")
      (value "Test_point")
      (footprint "fromST:TP_C40")
      (description "Test point")
      (fields (field (name "PUBLISHER") "Altium Limited"))
      (libsource (lib "Sajad_Altium_Library") (part "Test point"))
    )
    (comp (ref "TP105")
      (value "Test_point")
      (footprint "fromST:TP_C40")
      (description "Test point")
      (fields (field (name "PUBLISHER") "Altium Limited"))
      (libsource (lib "Sajad_Altium_Library") (part "Test point"))
    )
    (comp (ref "TP106")
      (value "Test_point")
      (footprint "fromST:TP_C40")
      (description "Test point")
      (fields (field (name "PUBLISHER") "Altium Limited"))
      (libsource (lib "Sajad_Altium_Library") (part "Test point"))
    )
    (comp (ref "TP107")
      (value "Test_point")
      (footprint "fromST:TP_C40")
      (description "Test point")
      (fields (field (name "PUBLISHER") "Altium Limited"))
      (libsource (lib "Sajad_Altium_Library") (part "Test point"))
    )
    (comp (ref "TP201")
      (value "Test_point")
      (footprint "fromST:TP_C40")
      (description "Test point")
      (fields (field (name "PUBLISHER") "Altium Limited"))
      (libsource (lib "Sajad_Altium_Library") (part "Test point"))
    )
    (comp (ref "TP202")
      (value "Test_point")
      (footprint "fromST:TP_C40")
      (description "Test point")
      (fields (field (name "PUBLISHER") "Altium Limited"))
      (libsource (lib "Sajad_Altium_Library") (part "Test point"))
    )
    (comp (ref "TP203")
      (value "Test_point")
      (footprint "fromST:TP_C40")
      (description "Test point")
      (fields (field (name "PUBLISHER") "Altium Limited"))
      (libsource (lib "Sajad_Altium_Library") (part "Test point"))
    )
    (comp (ref "TP204")
      (value "Test_point")
      (footprint "fromST:TP_C40")
      (description "Test point")
      (fields (field (name "PUBLISHER") "Altium Limited"))
      (libsource (lib "Sajad_Altium_Library") (part "Test point"))
    )
    (comp (ref "TP205")
      (value "Test_point")
      (footprint "fromST:TP_C40")
      (description "Test point")
      (fields (field (name "PUBLISHER") "Altium Limited"))
      (libsource (lib "Sajad_Altium_Library") (part "Test point"))
    )
    (comp (ref "TP206")
      (value "Test_point")
      (footprint "fromST:TP_C40")
      (description "Test point")
      (fields (field (name "PUBLISHER") "Altium Limited"))
      (libsource (lib "Sajad_Altium_Library") (part "Test point"))
    )
    (comp (ref "TP207")
      (value "Test_point")
      (footprint "fromST:TP_C40")
      (description "Test point")
      (fields (field (name "PUBLISHER") "Altium Limited"))
      (libsource (lib "Sajad_Altium_Library") (part "Test point"))
    )
  )
  (nets
    (net (code "1") (name "+15V") (class "Default")
      (node (ref "C1") (pin "1") (pinfunction "1_1") (pintype "passive"))
      (node (ref "C4") (pin "1") (pinfunction "1_1") (pintype "passive"))
      (node (ref "C5") (pin "1") (pinfunction "1_1") (pintype "passive"))
      (node (ref "C6") (pin "1") (pinfunction "1_1") (pintype "passive"))
      (node (ref "C7") (pin "1") (pinfunction "1_1") (pintype "passive"))
      (node (ref "C8") (pin "1") (pinfunction "1_1") (pintype "passive"))
      (node (ref "IC2") (pin "8") (pinfunction "VDD_8") (pintype "power_in"))
      (node (ref "IC3") (pin "8") (pinfunction "VDD_8") (pintype "power_in"))
      (node (ref "L1") (pin "2") (pinfunction "2_2") (pintype "passive"))
      (node (ref "LD2") (pin "2") (pinfunction "A_2") (pintype "passive"))
      (node (ref "M1") (pin "3") (pinfunction "VCC_3") (pintype "power_in"))
      (node (ref "R1") (pin "2") (pinfunction "2_2") (pintype "passive"))
      (node (ref "R2") (pin "1") (pinfunction "1_1") (pintype "passive"))
      (node (ref "TP1") (pin "1") (pinfunction "1_1") (pintype "passive"))
      (node (ref "TP3") (pin "1") (pinfunction "1_1") (pintype "passive"))
    )
    (net (code "2") (name "/COLLECTOR_A") (class "Default")
      (node (ref "D110") (pin "2") (pinfunction "2_2") (pintype "passive"))
      (node (ref "J3") (pin "1") (pinfunction "1_1") (pintype "bidirectional"))
      (node (ref "R110") (pin "2") (pinfunction "2_2") (pintype "passive"))
      (node (ref "TP106") (pin "1") (pinfunction "1_1") (pintype "passive"))
    )
    (net (code "3") (name "/COLLECTOR_B") (class "Default")
      (node (ref "D210") (pin "2") (pinfunction "2_2") (pintype "passive"))
      (node (ref "J5") (pin "1") (pinfunction "1_1") (pintype "bidirectional"))
      (node (ref "R210") (pin "2") (pinfunction "2_2") (pintype "passive"))
      (node (ref "TP206") (pin "1") (pinfunction "1_1") (pintype "passive"))
    )
    (net (code "4") (name "/EGND") (class "Default")
      (node (ref "J4") (pin "3") (pinfunction "3_3") (pintype "bidirectional"))
      (node (ref "R19") (pin "1") (pinfunction "1_1") (pintype "passive"))
      (node (ref "T1") (pin "2") (pinfunction "E_2") (pintype "passive"))
      (node (ref "TP10") (pin "1") (pinfunction "1_1") (pintype "passive"))
    )
    (net (code "5") (name "/EMITTER_A") (class "Default")
      (node (ref "C102") (pin "1") (pinfunction "1_1") (pintype "passive"))
      (node (ref "C103") (pin "1") (pinfunction "1_1") (pintype "passive"))
      (node (ref "C104") (pin "1") (pinfunction "1_1") (pintype "passive"))
      (node (ref "C105") (pin "1") (pinfunction "1_1") (pintype "passive"))
      (node (ref "C106") (pin "1") (pinfunction "1_1") (pintype "passive"))
      (node (ref "C107") (pin "1") (pinfunction "1_1") (pintype "passive"))
      (node (ref "C108") (pin "2") (pinfunction "2_2") (pintype "passive"))
      (node (ref "C109") (pin "2") (pinfunction "2_2") (pintype "passive"))
      (node (ref "C110") (pin "2") (pinfunction "2_2") (pintype "passive"))
      (node (ref "C111") (pin "2") (pinfunction "2_2") (pintype "passive"))
      (node (ref "C112") (pin "2") (pinfunction "2_2") (pintype "passive"))
      (node (ref "C113") (pin "2") (pinfunction "2_2") (pintype "passive"))
      (node (ref "J3") (pin "4") (pinfunction "4_4") (pintype "power_in"))
      (node (ref "M1") (pin "7") (pinfunction "VE1_7") (pintype "power_in"))
      (node (ref "TP102") (pin "1") (pinfunction "1_1") (pintype "passive"))
    )
    (net (code "6") (name "/EMITTER_B") (class "Default")
      (node (ref "C202") (pin "1") (pinfunction "1_1") (pintype "passive"))
      (node (ref "C203") (pin "1") (pinfunction "1_1") (pintype "passive"))
      (node (ref "C204") (pin "1") (pinfunction "1_1") (pintype "passive"))
      (node (ref "C205") (pin "1") (pinfunction "1_1") (pintype "passive"))
      (node (ref "C206") (pin "1") (pinfunction "1_1") (pintype "passive"))
      (node (ref "C207") (pin "1") (pinfunction "1_1") (pintype "passive"))
      (node (ref "C208") (pin "2") (pinfunction "2_2") (pintype "passive"))
      (node (ref "C209") (pin "2") (pinfunction "2_2") (pintype "passive"))
      (node (ref "C210") (pin "2") (pinfunction "2_2") (pintype "passive"))
      (node (ref "C211") (pin "2") (pinfunction "2_2") (pintype "passive"))
      (node (ref "C212") (pin "2") (pinfunction "2_2") (pintype "passive"))
      (node (ref "C213") (pin "2") (pinfunction "2_2") (pintype "passive"))
      (node (ref "J5") (pin "4") (pinfunction "4_4") (pintype "power_in"))
      (node (ref "M1") (pin "15") (pinfunction "VE2_15") (pintype "power_in"))
      (node (ref "TP202") (pin "1") (pinfunction "1_1") (pintype "passive"))
    )
    (net (code "7") (name "/ERROR_OUTPUT") (class "Default")
      (node (ref "J4") (pin "2") (pinfunction "2_2") (pintype "bidirectional"))
      (node (ref "R15") (pin "1") (pinfunction "1_1") (pintype "passive"))
      (node (ref "T1") (pin "3") (pinfunction "C_3") (pintype "passive"))
      (node (ref "TP13") (pin "1") (pinfunction "1_1") (pintype "passive"))
    )
    (net (code "8") (name "/EVCC") (class "Default")
      (node (ref "J4") (pin "1") (pinfunction "1_1") (pintype "bidirectional"))
      (node (ref "R14") (pin "2") (pinfunction "2_2") (pintype "passive"))
      (node (ref "R15") (pin "2") (pinfunction "2_2") (pintype "passive"))
      (node (ref "TP8") (pin "1") (pinfunction "1_1") (pintype "passive"))
    )
    (net (code "9") (name "/IN_A_N") (class "Default")
      (node (ref "D4") (pin "2") (pinfunction "A_2") (pintype "passive"))
      (node (ref "J2") (pin "2") (pinfunction "2_2") (pintype "bidirectional"))
      (node (ref "TP14") (pin "1") (pinfunction "1_1") (pintype "passive"))
    )
    (net (code "10") (name "/IN_A_P") (class "Default")
      (node (ref "J2") (pin "1") (pinfunction "1_1") (pintype "bidirectional"))
      (node (ref "R4") (pin "1") (pinfunction "1_1") (pintype "passive"))
      (node (ref "R6") (pin "1") (pinfunction "1_1") (pintype "passive"))
      (node (ref "TP12") (pin "1") (pinfunction "1_1") (pintype "passive"))
    )
    (net (code "11") (name "/IN_B_N") (class "Default")
      (node (ref "D5") (pin "2") (pinfunction "A_2") (pintype "passive"))
      (node (ref "J2") (pin "4") (pinfunction "4_4") (pintype "bidirectional"))
      (node (ref "TP17") (pin "1") (pinfunction "1_1") (pintype "passive"))
    )
    (net (code "12") (name "/IN_B_P") (class "Default")
      (node (ref "J2") (pin "3") (pinfunction "3_3") (pintype "bidirectional"))
      (node (ref "R11") (pin "1") (pinfunction "1_1") (pintype "passive"))
      (node (ref "R9") (pin "1") (pinfunction "1_1") (pintype "passive"))
      (node (ref "TP15") (pin "1") (pinfunction "1_1") (pintype "passive"))
    )
    (net (code "13") (name "/VIN") (class "Default")
      (node (ref "D1") (pin "2") (pinfunction "A_2") (pintype "passive"))
      (node (ref "D2") (pin "1") (pinfunction "C_1") (pintype "passive"))
      (node (ref "J1") (pin "1") (pinfunction "1_1") (pintype "power_in"))
      (node (ref "TP2") (pin "1") (pinfunction "1_1") (pintype "passive"))
    )
    (net (code "14") (name "COM_A") (class "Default")
      (node (ref "C101") (pin "2") (pinfunction "2_2") (pintype "passive"))
      (node (ref "C108") (pin "1") (pinfunction "1_1") (pintype "passive"))
      (node (ref "C109") (pin "1") (pinfunction "1_1") (pintype "passive"))
      (node (ref "C110") (pin "1") (pinfunction "1_1") (pintype "passive"))
      (node (ref "C111") (pin "1") (pinfunction "1_1") (pintype "passive"))
      (node (ref "C112") (pin "1") (pinfunction "1_1") (pintype "passive"))
      (node (ref "C113") (pin "1") (pinfunction "1_1") (pintype "passive"))
      (node (ref "D101") (pin "2") (pinfunction "A_2") (pintype "passive"))
      (node (ref "M1") (pin "13") (pinfunction "COM1_13") (pintype "power_in"))
      (node (ref "R113") (pin "2") (pinfunction "2_2") (pintype "passive"))
      (node (ref "TP103") (pin "1") (pinfunction "1_1") (pintype "passive"))
    )
    (net (code "15") (name "COM_B") (class "Default")
      (node (ref "C201") (pin "2") (pinfunction "2_2") (pintype "passive"))
      (node (ref "C208") (pin "1") (pinfunction "1_1") (pintype "passive"))
      (node (ref "C209") (pin "1") (pinfunction "1_1") (pintype "passive"))
      (node (ref "C210") (pin "1") (pinfunction "1_1") (pintype "passive"))
      (node (ref "C211") (pin "1") (pinfunction "1_1") (pintype "passive"))
      (node (ref "C212") (pin "1") (pinfunction "1_1") (pintype "passive"))
      (node (ref "C213") (pin "1") (pinfunction "1_1") (pintype "passive"))
      (node (ref "D201") (pin "2") (pinfunction "A_2") (pintype "passive"))
      (node (ref "M1") (pin "21") (pinfunction "COM2_21") (pintype "power_in"))
      (node (ref "R213") (pin "2") (pinfunction "2_2") (pintype "passive"))
      (node (ref "TP203") (pin "1") (pinfunction "1_1") (pintype "passive"))
    )
    (net (code "16") (name "GATE_A") (class "Default")
      (node (ref "D102") (pin "1") (pinfunction "C_1") (pintype "passive"))
      (node (ref "D112") (pin "2") (pinfunction "A_2") (pintype "passive"))
      (node (ref "J3") (pin "3") (pinfunction "3_3") (pintype "bidirectional"))
      (node (ref "R111") (pin "2") (pinfunction "2_2") (pintype "passive"))
      (node (ref "R114") (pin "2") (pinfunction "2_2") (pintype "passive"))
      (node (ref "TP107") (pin "1") (pinfunction "1_1") (pintype "passive"))
    )
    (net (code "17") (name "GATE_B") (class "Default")
      (node (ref "D202") (pin "1") (pinfunction "C_1") (pintype "passive"))
      (node (ref "D212") (pin "2") (pinfunction "A_2") (pintype "passive"))
      (node (ref "J5") (pin "3") (pinfunction "3_3") (pintype "bidirectional"))
      (node (ref "R211") (pin "2") (pinfunction "2_2") (pintype "passive"))
      (node (ref "R214") (pin "2") (pinfunction "2_2") (pintype "passive"))
      (node (ref "TP207") (pin "1") (pinfunction "1_1") (pintype "passive"))
    )
    (net (code "18") (name "GND") (class "Default")
      (node (ref "C2") (pin "2") (pinfunction "2_2") (pintype "passive"))
      (node (ref "C3") (pin "2") (pinfunction "2_2") (pintype "passive"))
      (node (ref "C4") (pin "2") (pinfunction "2_2") (pintype "passive"))
      (node (ref "C5") (pin "2") (pinfunction "2_2") (pintype "passive"))
      (node (ref "C6") (pin "2") (pinfunction "2_2") (pintype "passive"))
      (node (ref "C7") (pin "2") (pinfunction "2_2") (pintype "passive"))
      (node (ref "C8") (pin "2") (pinfunction "2_2") (pintype "passive"))
      (node (ref "D2") (pin "2") (pinfunction "A_2") (pintype "passive"))
      (node (ref "D3") (pin "2") (pinfunction "A_2") (pintype "passive"))
      (node (ref "IC1") (pin "3") (pinfunction "GND_3") (pintype "passive"))
      (node (ref "IC1") (pin "5") (pinfunction "ON/OFF_5") (pintype "input"))
      (node (ref "IC2") (pin "5") (pinfunction "VSS_5") (pintype "power_in"))
      (node (ref "IC3") (pin "5") (pinfunction "VSS_5") (pintype "power_in"))
      (node (ref "J1") (pin "2") (pinfunction "2_2") (pintype "power_in"))
      (node (ref "LD1") (pin "1") (pinfunction "C_1") (pintype "passive"))
      (node (ref "M1") (pin "4") (pinfunction "GND_4") (pintype "power_in"))
      (node (ref "R17") (pin "1") (pinfunction "1_1") (pintype "passive"))
      (node (ref "R3") (pin "1") (pinfunction "1_1") (pintype "passive"))
      (node (ref "TP18") (pin "1") (pinfunction "1_1") (pintype "passive"))
      (node (ref "TP19") (pin "1") (pinfunction "1_1") (pintype "passive"))
    )
    (net (code "19") (name "Net-(D1-C)") (class "Default")
      (node (ref "C2") (pin "1") (pinfunction "1_1") (pintype "passive"))
      (node (ref "C3") (pin "1") (pinfunction "1_1") (pintype "passive"))
      (node (ref "D1") (pin "1") (pinfunction "C_1") (pintype "passive"))
      (node (ref "IC1") (pin "1") (pinfunction "VIN_1") (pintype "input"))
    )
    (net (code "20") (name "Net-(D3-C)") (class "Default")
      (node (ref "D3") (pin "1") (pinfunction "C_1") (pintype "passive"))
      (node (ref "IC1") (pin "2") (pinfunction "OUTPUT_2") (pintype "output"))
      (node (ref "L1") (pin "1") (pinfunction "1_1") (pintype "passive"))
    )
    (net (code "21") (name "Net-(D4-C)") (class "Default")
      (node (ref "D4") (pin "1") (pinfunction "C_1") (pintype "passive"))
      (node (ref "IC2") (pin "3") (pinfunction "K_3") (pintype "input"))
      (node (ref "R8") (pin "1") (pinfunction "1_1") (pintype "passive"))
      (node (ref "TP6") (pin "1") (pinfunction "1_1") (pintype "passive"))
    )
    (net (code "22") (name "Net-(D5-C)") (class "Default")
      (node (ref "D5") (pin "1") (pinfunction "C_1") (pintype "passive"))
      (node (ref "IC3") (pin "3") (pinfunction "K_3") (pintype "input"))
      (node (ref "R13") (pin "1") (pinfunction "1_1") (pintype "passive"))
      (node (ref "TP11") (pin "1") (pinfunction "1_1") (pintype "passive"))
    )
    (net (code "23") (name "Net-(D101-C)") (class "Default")
      (node (ref "D101") (pin "1") (pinfunction "C_1") (pintype "passive"))
      (node (ref "D102") (pin "2") (pinfunction "A_2") (pintype "passive"))
      (node (ref "D103") (pin "2") (pinfunction "A_2") (pintype "passive"))
      (node (ref "R101") (pin "2") (pinfunction "2_2") (pintype "passive"))
    )
    (net (code "24") (name "Net-(D103-C)") (class "Default")
      (node (ref "D103") (pin "1") (pinfunction "C_1") (pintype "passive"))
      (node (ref "D104") (pin "2") (pinfunction "A_2") (pintype "passive"))
    )
    (net (code "25") (name "Net-(D104-C)") (class "Default")
      (node (ref "D104") (pin "1") (pinfunction "C_1") (pintype "passive"))
      (node (ref "D105") (pin "2") (pinfunction "A_2") (pintype "passive"))
    )
    (net (code "26") (name "Net-(D105-C)") (class "Default")
      (node (ref "D105") (pin "1") (pinfunction "C_1") (pintype "passive"))
      (node (ref "D106") (pin "2") (pinfunction "A_2") (pintype "passive"))
    )
    (net (code "27") (name "Net-(D106-C)") (class "Default")
      (node (ref "D106") (pin "1") (pinfunction "C_1") (pintype "passive"))
      (node (ref "D107") (pin "2") (pinfunction "A_2") (pintype "passive"))
    )
    (net (code "28") (name "Net-(D107-C)") (class "Default")
      (node (ref "D107") (pin "1") (pinfunction "C_1") (pintype "passive"))
      (node (ref "D108") (pin "2") (pinfunction "A_2") (pintype "passive"))
    )
    (net (code "29") (name "Net-(D108-C)") (class "Default")
      (node (ref "D108") (pin "1") (pinfunction "C_1") (pintype "passive"))
      (node (ref "D109") (pin "2") (pinfunction "A_2") (pintype "passive"))
    )
    (net (code "30") (name "Net-(D109-C)") (class "Default")
      (node (ref "D109") (pin "1") (pinfunction "C_1") (pintype "passive"))
      (node (ref "D110") (pin "1") (pinfunction "1_1") (pintype "passive"))
    )
    (net (code "31") (name "Net-(D111-A)") (class "Default")
      (node (ref "D111") (pin "2") (pinfunction "A_2") (pintype "passive"))
      (node (ref "R102") (pin "2") (pinfunction "2_2") (pintype "passive"))
      (node (ref "R103") (pin "1") (pinfunction "1_1") (pintype "passive"))
    )
    (net (code "32") (name "Net-(D201-C)") (class "Default")
      (node (ref "D201") (pin "1") (pinfunction "C_1") (pintype "passive"))
      (node (ref "D202") (pin "2") (pinfunction "A_2") (pintype "passive"))
      (node (ref "D203") (pin "2") (pinfunction "A_2") (pintype "passive"))
      (node (ref "R201") (pin "2") (pinfunction "2_2") (pintype "passive"))
    )
    (net (code "33") (name "Net-(D203-C)") (class "Default")
      (node (ref "D203") (pin "1") (pinfunction "C_1") (pintype "passive"))
      (node (ref "D204") (pin "2") (pinfunction "A_2") (pintype "passive"))
    )
    (net (code "34") (name "Net-(D204-C)") (class "Default")
      (node (ref "D204") (pin "1") (pinfunction "C_1") (pintype "passive"))
      (node (ref "D205") (pin "2") (pinfunction "A_2") (pintype "passive"))
    )
    (net (code "35") (name "Net-(D205-C)") (class "Default")
      (node (ref "D205") (pin "1") (pinfunction "C_1") (pintype "passive"))
      (node (ref "D206") (pin "2") (pinfunction "A_2") (pintype "passive"))
    )
    (net (code "36") (name "Net-(D206-C)") (class "Default")
      (node (ref "D206") (pin "1") (pinfunction "C_1") (pintype "passive"))
      (node (ref "D207") (pin "2") (pinfunction "A_2") (pintype "passive"))
    )
    (net (code "37") (name "Net-(D207-C)") (class "Default")
      (node (ref "D207") (pin "1") (pinfunction "C_1") (pintype "passive"))
      (node (ref "D208") (pin "2") (pinfunction "A_2") (pintype "passive"))
    )
    (net (code "38") (name "Net-(D208-C)") (class "Default")
      (node (ref "D208") (pin "1") (pinfunction "C_1") (pintype "passive"))
      (node (ref "D209") (pin "2") (pinfunction "A_2") (pintype "passive"))
    )
    (net (code "39") (name "Net-(D209-C)") (class "Default")
      (node (ref "D209") (pin "1") (pinfunction "C_1") (pintype "passive"))
      (node (ref "D210") (pin "1") (pinfunction "1_1") (pintype "passive"))
    )
    (net (code "40") (name "Net-(D211-A)") (class "Default")
      (node (ref "D211") (pin "2") (pinfunction "A_2") (pintype "passive"))
      (node (ref "R202") (pin "2") (pinfunction "2_2") (pintype "passive"))
      (node (ref "R203") (pin "1") (pinfunction "1_1") (pintype "passive"))
    )
    (net (code "41") (name "Net-(IC1-FEEDBACK)") (class "Default")
      (node (ref "C1") (pin "2") (pinfunction "2_2") (pintype "passive"))
      (node (ref "IC1") (pin "4") (pinfunction "FEEDBACK_4") (pintype "input"))
      (node (ref "R1") (pin "1") (pinfunction "1_1") (pintype "passive"))
      (node (ref "R3") (pin "2") (pinfunction "2_2") (pintype "passive"))
    )
    (net (code "42") (name "Net-(IC2-A)") (class "Default")
      (node (ref "IC2") (pin "2") (pinfunction "A_2") (pintype "input"))
      (node (ref "R5") (pin "2") (pinfunction "2_2") (pintype "passive"))
      (node (ref "R7") (pin "2") (pinfunction "2_2") (pintype "passive"))
      (node (ref "R8") (pin "2") (pinfunction "2_2") (pintype "passive"))
      (node (ref "TP4") (pin "1") (pinfunction "1_1") (pintype "passive"))
    )
    (net (code "43") (name "Net-(IC2-VO1)") (class "Default")
      (node (ref "IC2") (pin "6") (pinfunction "VO1_6") (pintype "bidirectional"))
      (node (ref "IC2") (pin "7") (pinfunction "VO2_7") (pintype "bidirectional"))
      (node (ref "M1") (pin "6") (pinfunction "INA_6") (pintype "input"))
      (node (ref "TP5") (pin "1") (pinfunction "1_1") (pintype "passive"))
    )
    (net (code "44") (name "Net-(IC3-A)") (class "Default")
      (node (ref "IC3") (pin "2") (pinfunction "A_2") (pintype "input"))
      (node (ref "R10") (pin "2") (pinfunction "2_2") (pintype "passive"))
      (node (ref "R12") (pin "2") (pinfunction "2_2") (pintype "passive"))
      (node (ref "R13") (pin "2") (pinfunction "2_2") (pintype "passive"))
      (node (ref "TP7") (pin "1") (pinfunction "1_1") (pintype "passive"))
    )
    (net (code "45") (name "Net-(IC3-VO1)") (class "Default")
      (node (ref "IC3") (pin "6") (pinfunction "VO1_6") (pintype "bidirectional"))
      (node (ref "IC3") (pin "7") (pinfunction "VO2_7") (pintype "bidirectional"))
      (node (ref "M1") (pin "5") (pinfunction "INB_5") (pintype "input"))
      (node (ref "TP9") (pin "1") (pinfunction "1_1") (pintype "passive"))
    )
    (net (code "46") (name "Net-(IC4-A)") (class "Default")
      (node (ref "IC4") (pin "1") (pinfunction "A_1") (pintype "input"))
      (node (ref "LD2") (pin "1") (pinfunction "C_1") (pintype "passive"))
      (node (ref "R16") (pin "2") (pinfunction "2_2") (pintype "passive"))
    )
    (net (code "47") (name "Net-(IC4-C-Pad2)") (class "Default")
      (node (ref "IC4") (pin "2") (pinfunction "C_2") (pintype "input"))
      (node (ref "R16") (pin "1") (pinfunction "1_1") (pintype "passive"))
      (node (ref "R18") (pin "2") (pinfunction "2_2") (pintype "passive"))
    )
    (net (code "48") (name "Net-(IC4-C-Pad4)") (class "Default")
      (node (ref "IC4") (pin "4") (pinfunction "C_4") (pintype "open_collector"))
      (node (ref "R14") (pin "1") (pinfunction "1_1") (pintype "passive"))
    )
    (net (code "49") (name "Net-(IC4-E)") (class "Default")
      (node (ref "IC4") (pin "3") (pinfunction "E_3") (pintype "open_emitter"))
      (node (ref "R19") (pin "2") (pinfunction "2_2") (pintype "passive"))
      (node (ref "T1") (pin "1") (pinfunction "B_1") (pintype "passive"))
    )
    (net (code "50") (name "Net-(LD1-A)") (class "Default")
      (node (ref "LD1") (pin "2") (pinfunction "A_2") (pintype "passive"))
      (node (ref "R2") (pin "2") (pinfunction "2_2") (pintype "passive"))
    )
    (net (code "51") (name "Net-(M1A-SO)") (class "Default")
      (node (ref "M1") (pin "2") (pinfunction "SO_2") (pintype "open_collector"))
      (node (ref "R18") (pin "1") (pinfunction "1_1") (pintype "passive"))
      (node (ref "TP16") (pin "1") (pinfunction "1_1") (pintype "passive"))
    )
    (net (code "52") (name "Net-(M1A-TB)") (class "Default")
      (node (ref "M1") (pin "1") (pinfunction "TB_1") (pintype "input"))
      (node (ref "R17") (pin "2") (pinfunction "2_2") (pintype "passive"))
    )
    (net (code "53") (name "Net-(M1B-ACL1)") (class "Default")
      (node (ref "M1") (pin "14") (pinfunction "ACL1_14") (pintype "input"))
      (node (ref "R101") (pin "1") (pinfunction "1_1") (pintype "passive"))
    )
    (net (code "54") (name "Net-(M1B-GH1)") (class "Default")
      (node (ref "M1") (pin "10") (pinfunction "GH1_10") (pintype "open_emitter"))
      (node (ref "R111") (pin "1") (pinfunction "1_1") (pintype "passive"))
      (node (ref "TP104") (pin "1") (pinfunction "1_1") (pintype "passive"))
    )
    (net (code "55") (name "Net-(M1B-GL1)") (class "Default")
      (node (ref "M1") (pin "12") (pinfunction "GL1_12") (pintype "open_collector"))
      (node (ref "R113") (pin "1") (pinfunction "1_1") (pintype "passive"))
      (node (ref "R114") (pin "1") (pinfunction "1_1") (pintype "passive"))
      (node (ref "TP105") (pin "1") (pinfunction "1_1") (pintype "passive"))
    )
    (net (code "56") (name "Net-(M1B-SOA1)") (class "Default")
      (node (ref "M1") (pin "8") (pinfunction "SOA1_8") (pintype "open_collector"))
      (node (ref "R112") (pin "1") (pinfunction "1_1") (pintype "passive"))
    )
    (net (code "57") (name "Net-(M1B-VCE1)") (class "Default")
      (node (ref "C101") (pin "1") (pinfunction "1_1") (pintype "passive"))
      (node (ref "M1") (pin "11") (pinfunction "VCE1_11") (pintype "input"))
      (node (ref "R102") (pin "1") (pinfunction "1_1") (pintype "passive"))
    )
    (net (code "58") (name "Net-(M1C-ACL2)") (class "Default")
      (node (ref "M1") (pin "22") (pinfunction "ACL2_22") (pintype "input"))
      (node (ref "R201") (pin "1") (pinfunction "1_1") (pintype "passive"))
    )
    (net (code "59") (name "Net-(M1C-GH2)") (class "Default")
      (node (ref "M1") (pin "18") (pinfunction "GH2_18") (pintype "open_emitter"))
      (node (ref "R211") (pin "1") (pinfunction "1_1") (pintype "passive"))
      (node (ref "TP204") (pin "1") (pinfunction "1_1") (pintype "passive"))
    )
    (net (code "60") (name "Net-(M1C-GL2)") (class "Default")
      (node (ref "M1") (pin "20") (pinfunction "GL2_20") (pintype "open_collector"))
      (node (ref "R213") (pin "1") (pinfunction "1_1") (pintype "passive"))
      (node (ref "R214") (pin "1") (pinfunction "1_1") (pintype "passive"))
      (node (ref "TP205") (pin "1") (pinfunction "1_1") (pintype "passive"))
    )
    (net (code "61") (name "Net-(M1C-SOA2)") (class "Default")
      (node (ref "M1") (pin "16") (pinfunction "SOA2_16") (pintype "open_collector"))
      (node (ref "R212") (pin "1") (pinfunction "1_1") (pintype "passive"))
    )
    (net (code "62") (name "Net-(M1C-VCE2)") (class "Default")
      (node (ref "C201") (pin "1") (pinfunction "1_1") (pintype "passive"))
      (node (ref "M1") (pin "19") (pinfunction "VCE2_19") (pintype "input"))
      (node (ref "R202") (pin "1") (pinfunction "1_1") (pintype "passive"))
    )
    (net (code "63") (name "Net-(R4-Pad2)") (class "Default")
      (node (ref "R4") (pin "2") (pinfunction "2_2") (pintype "passive"))
      (node (ref "R5") (pin "1") (pinfunction "1_1") (pintype "passive"))
      (node (ref "R6") (pin "2") (pinfunction "2_2") (pintype "passive"))
      (node (ref "R7") (pin "1") (pinfunction "1_1") (pintype "passive"))
    )
    (net (code "64") (name "Net-(R10-Pad1)") (class "Default")
      (node (ref "R10") (pin "1") (pinfunction "1_1") (pintype "passive"))
      (node (ref "R11") (pin "2") (pinfunction "2_2") (pintype "passive"))
      (node (ref "R12") (pin "1") (pinfunction "1_1") (pintype "passive"))
      (node (ref "R9") (pin "2") (pinfunction "2_2") (pintype "passive"))
    )
    (net (code "65") (name "Net-(R103-Pad2)") (class "Default")
      (node (ref "R103") (pin "2") (pinfunction "2_2") (pintype "passive"))
      (node (ref "R104") (pin "1") (pinfunction "1_1") (pintype "passive"))
    )
    (net (code "66") (name "Net-(R104-Pad2)") (class "Default")
      (node (ref "R104") (pin "2") (pinfunction "2_2") (pintype "passive"))
      (node (ref "R105") (pin "1") (pinfunction "1_1") (pintype "passive"))
    )
    (net (code "67") (name "Net-(R105-Pad2)") (class "Default")
      (node (ref "R105") (pin "2") (pinfunction "2_2") (pintype "passive"))
      (node (ref "R106") (pin "1") (pinfunction "1_1") (pintype "passive"))
    )
    (net (code "68") (name "Net-(R106-Pad2)") (class "Default")
      (node (ref "R106") (pin "2") (pinfunction "2_2") (pintype "passive"))
      (node (ref "R107") (pin "1") (pinfunction "1_1") (pintype "passive"))
    )
    (net (code "69") (name "Net-(R107-Pad2)") (class "Default")
      (node (ref "R107") (pin "2") (pinfunction "2_2") (pintype "passive"))
      (node (ref "R108") (pin "1") (pinfunction "1_1") (pintype "passive"))
    )
    (net (code "70") (name "Net-(R108-Pad2)") (class "Default")
      (node (ref "R108") (pin "2") (pinfunction "2_2") (pintype "passive"))
      (node (ref "R109") (pin "1") (pinfunction "1_1") (pintype "passive"))
    )
    (net (code "71") (name "Net-(R109-Pad2)") (class "Default")
      (node (ref "R109") (pin "2") (pinfunction "2_2") (pintype "passive"))
      (node (ref "R110") (pin "1") (pinfunction "1_1") (pintype "passive"))
    )
    (net (code "72") (name "Net-(R203-Pad2)") (class "Default")
      (node (ref "R203") (pin "2") (pinfunction "2_2") (pintype "passive"))
      (node (ref "R204") (pin "1") (pinfunction "1_1") (pintype "passive"))
    )
    (net (code "73") (name "Net-(R204-Pad2)") (class "Default")
      (node (ref "R204") (pin "2") (pinfunction "2_2") (pintype "passive"))
      (node (ref "R205") (pin "1") (pinfunction "1_1") (pintype "passive"))
    )
    (net (code "74") (name "Net-(R205-Pad2)") (class "Default")
      (node (ref "R205") (pin "2") (pinfunction "2_2") (pintype "passive"))
      (node (ref "R206") (pin "1") (pinfunction "1_1") (pintype "passive"))
    )
    (net (code "75") (name "Net-(R206-Pad2)") (class "Default")
      (node (ref "R206") (pin "2") (pinfunction "2_2") (pintype "passive"))
      (node (ref "R207") (pin "1") (pinfunction "1_1") (pintype "passive"))
    )
    (net (code "76") (name "Net-(R207-Pad2)") (class "Default")
      (node (ref "R207") (pin "2") (pinfunction "2_2") (pintype "passive"))
      (node (ref "R208") (pin "1") (pinfunction "1_1") (pintype "passive"))
    )
    (net (code "77") (name "Net-(R208-Pad2)") (class "Default")
      (node (ref "R208") (pin "2") (pinfunction "2_2") (pintype "passive"))
      (node (ref "R209") (pin "1") (pinfunction "1_1") (pintype "passive"))
    )
    (net (code "78") (name "Net-(R209-Pad2)") (class "Default")
      (node (ref "R209") (pin "2") (pinfunction "2_2") (pintype "passive"))
      (node (ref "R210") (pin "1") (pinfunction "1_1") (pintype "passive"))
    )
    (net (code "79") (name "VISO_A") (class "Default")
      (node (ref "C102") (pin "2") (pinfunction "2_2") (pintype "passive"))
      (node (ref "C103") (pin "2") (pinfunction "2_2") (pintype "passive"))
      (node (ref "C104") (pin "2") (pinfunction "2_2") (pintype "passive"))
      (node (ref "C105") (pin "2") (pinfunction "2_2") (pintype "passive"))
      (node (ref "C106") (pin "2") (pinfunction "2_2") (pintype "passive"))
      (node (ref "C107") (pin "2") (pinfunction "2_2") (pintype "passive"))
      (node (ref "D111") (pin "1") (pinfunction "C_1") (pintype "passive"))
      (node (ref "D112") (pin "1") (pinfunction "C_1") (pintype "passive"))
      (node (ref "M1") (pin "9") (pinfunction "VISO1_9") (pintype "power_in"))
      (node (ref "R112") (pin "2") (pinfunction "2_2") (pintype "passive"))
      (node (ref "TP101") (pin "1") (pinfunction "1_1") (pintype "passive"))
    )
    (net (code "80") (name "VISO_B") (class "Default")
      (node (ref "C202") (pin "2") (pinfunction "2_2") (pintype "passive"))
      (node (ref "C203") (pin "2") (pinfunction "2_2") (pintype "passive"))
      (node (ref "C204") (pin "2") (pinfunction "2_2") (pintype "passive"))
      (node (ref "C205") (pin "2") (pinfunction "2_2") (pintype "passive"))
      (node (ref "C206") (pin "2") (pinfunction "2_2") (pintype "passive"))
      (node (ref "C207") (pin "2") (pinfunction "2_2") (pintype "passive"))
      (node (ref "D211") (pin "1") (pinfunction "C_1") (pintype "passive"))
      (node (ref "D212") (pin "1") (pinfunction "C_1") (pintype "passive"))
      (node (ref "M1") (pin "17") (pinfunction "VISO2_17") (pintype "power_in"))
      (node (ref "R212") (pin "2") (pinfunction "2_2") (pintype "passive"))
      (node (ref "TP201") (pin "1") (pinfunction "1_1") (pintype "passive"))
    )
    (net (code "81") (name "unconnected-(IC2-NC-Pad1)") (class "Default")
      (node (ref "IC2") (pin "1") (pinfunction "NC_1") (pintype "power_in"))
    )
    (net (code "82") (name "unconnected-(IC2-NC-Pad4)") (class "Default")
      (node (ref "IC2") (pin "4") (pinfunction "NC_4") (pintype "passive"))
    )
    (net (code "83") (name "unconnected-(IC3-NC-Pad1)") (class "Default")
      (node (ref "IC3") (pin "1") (pinfunction "NC_1") (pintype "power_in"))
    )
    (net (code "84") (name "unconnected-(IC3-NC-Pad4)") (class "Default")
      (node (ref "IC3") (pin "4") (pinfunction "NC_4") (pintype "passive"))
    )
    (net (code "85") (name "unconnected-(J3-Pad2)") (class "Default")
      (node (ref "J3") (pin "2") (pinfunction "2_2") (pintype "bidirectional+no_connect"))
    )
    (net (code "86") (name "unconnected-(J5-Pad2)") (class "Default")
      (node (ref "J5") (pin "2") (pinfunction "2_2") (pintype "bidirectional+no_connect"))
    )
  )
)
